# quad.net
KiCad netlist of a schematic drawn in EAGLE
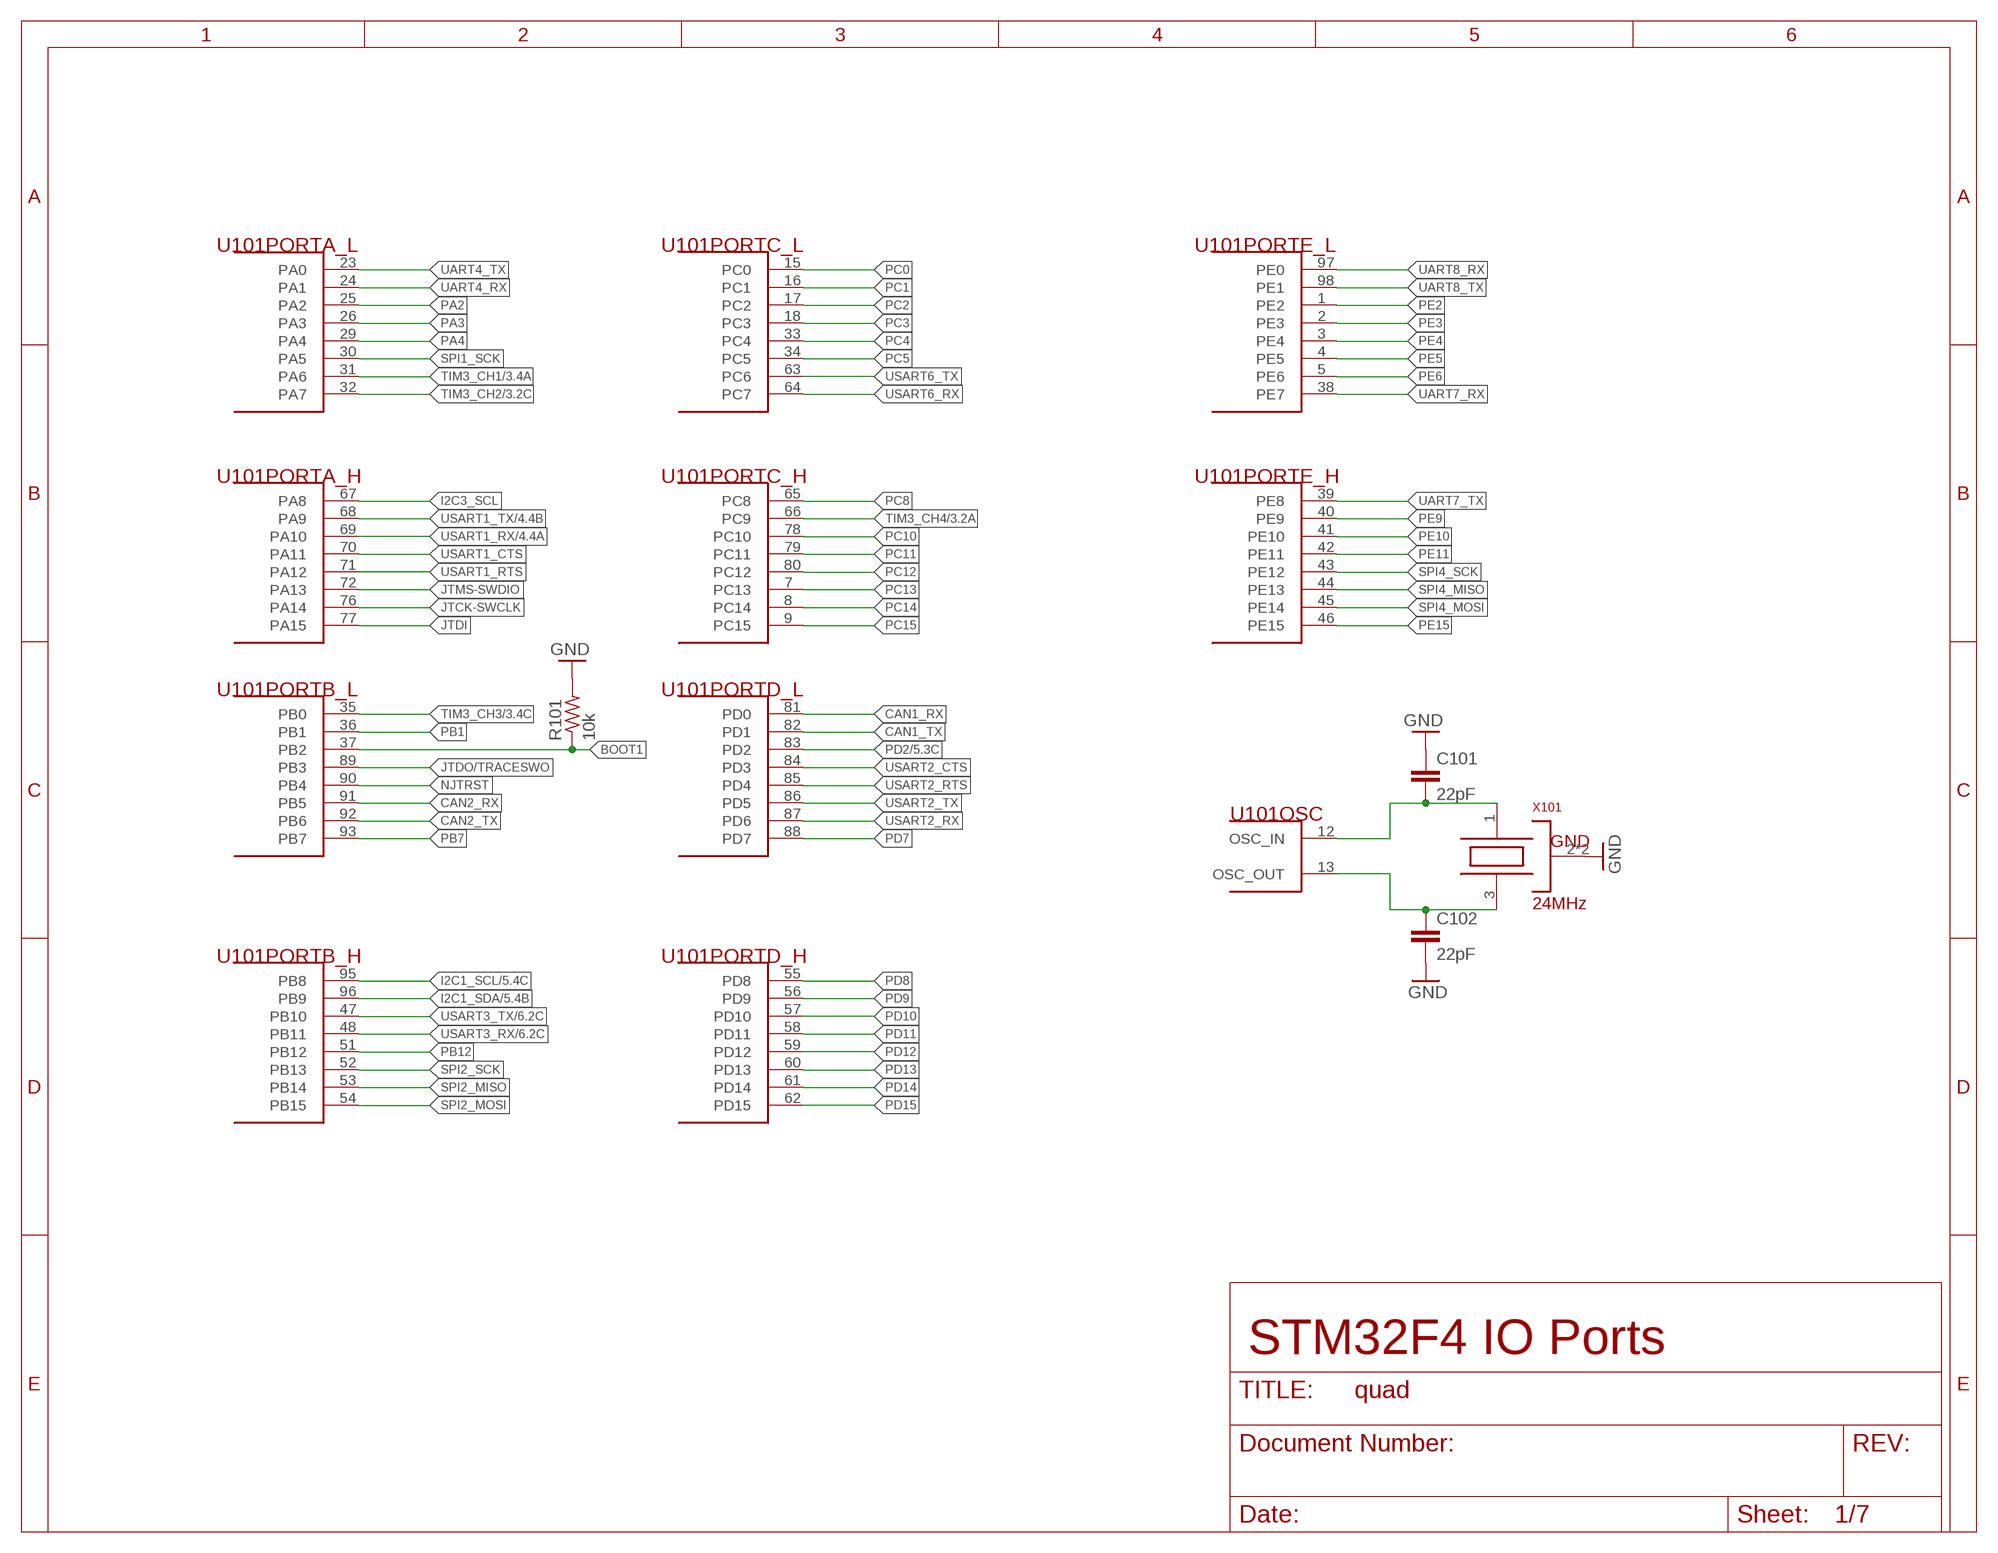
[diagram p0: schematic, sheet 1]
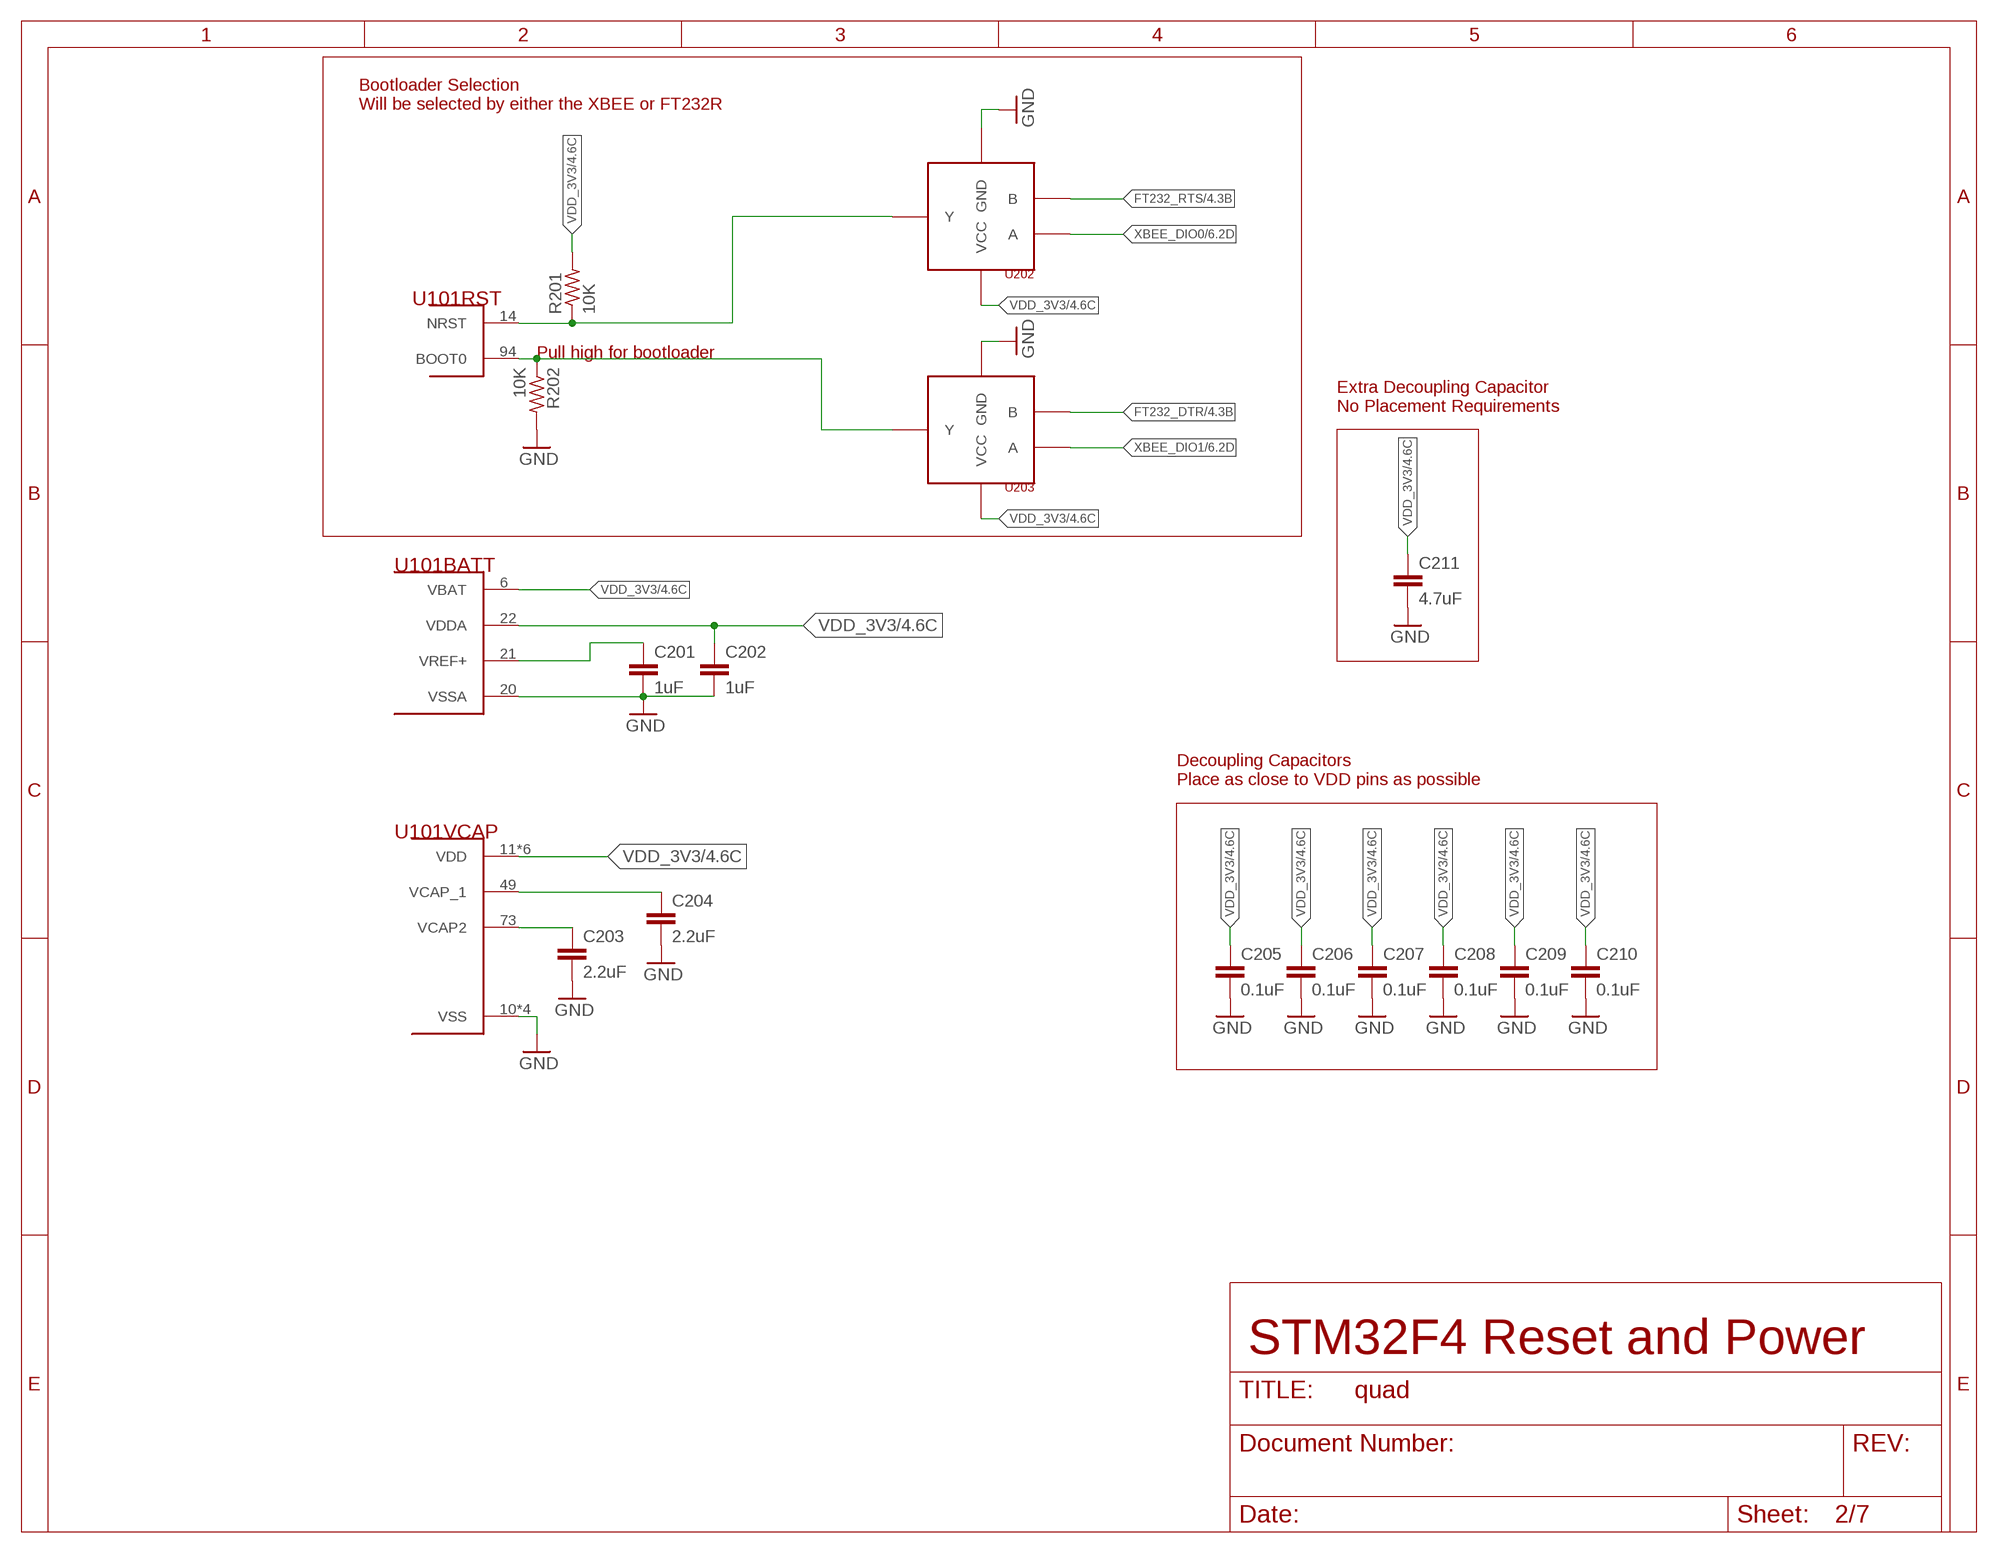
[diagram p1: schematic, sheet 2]
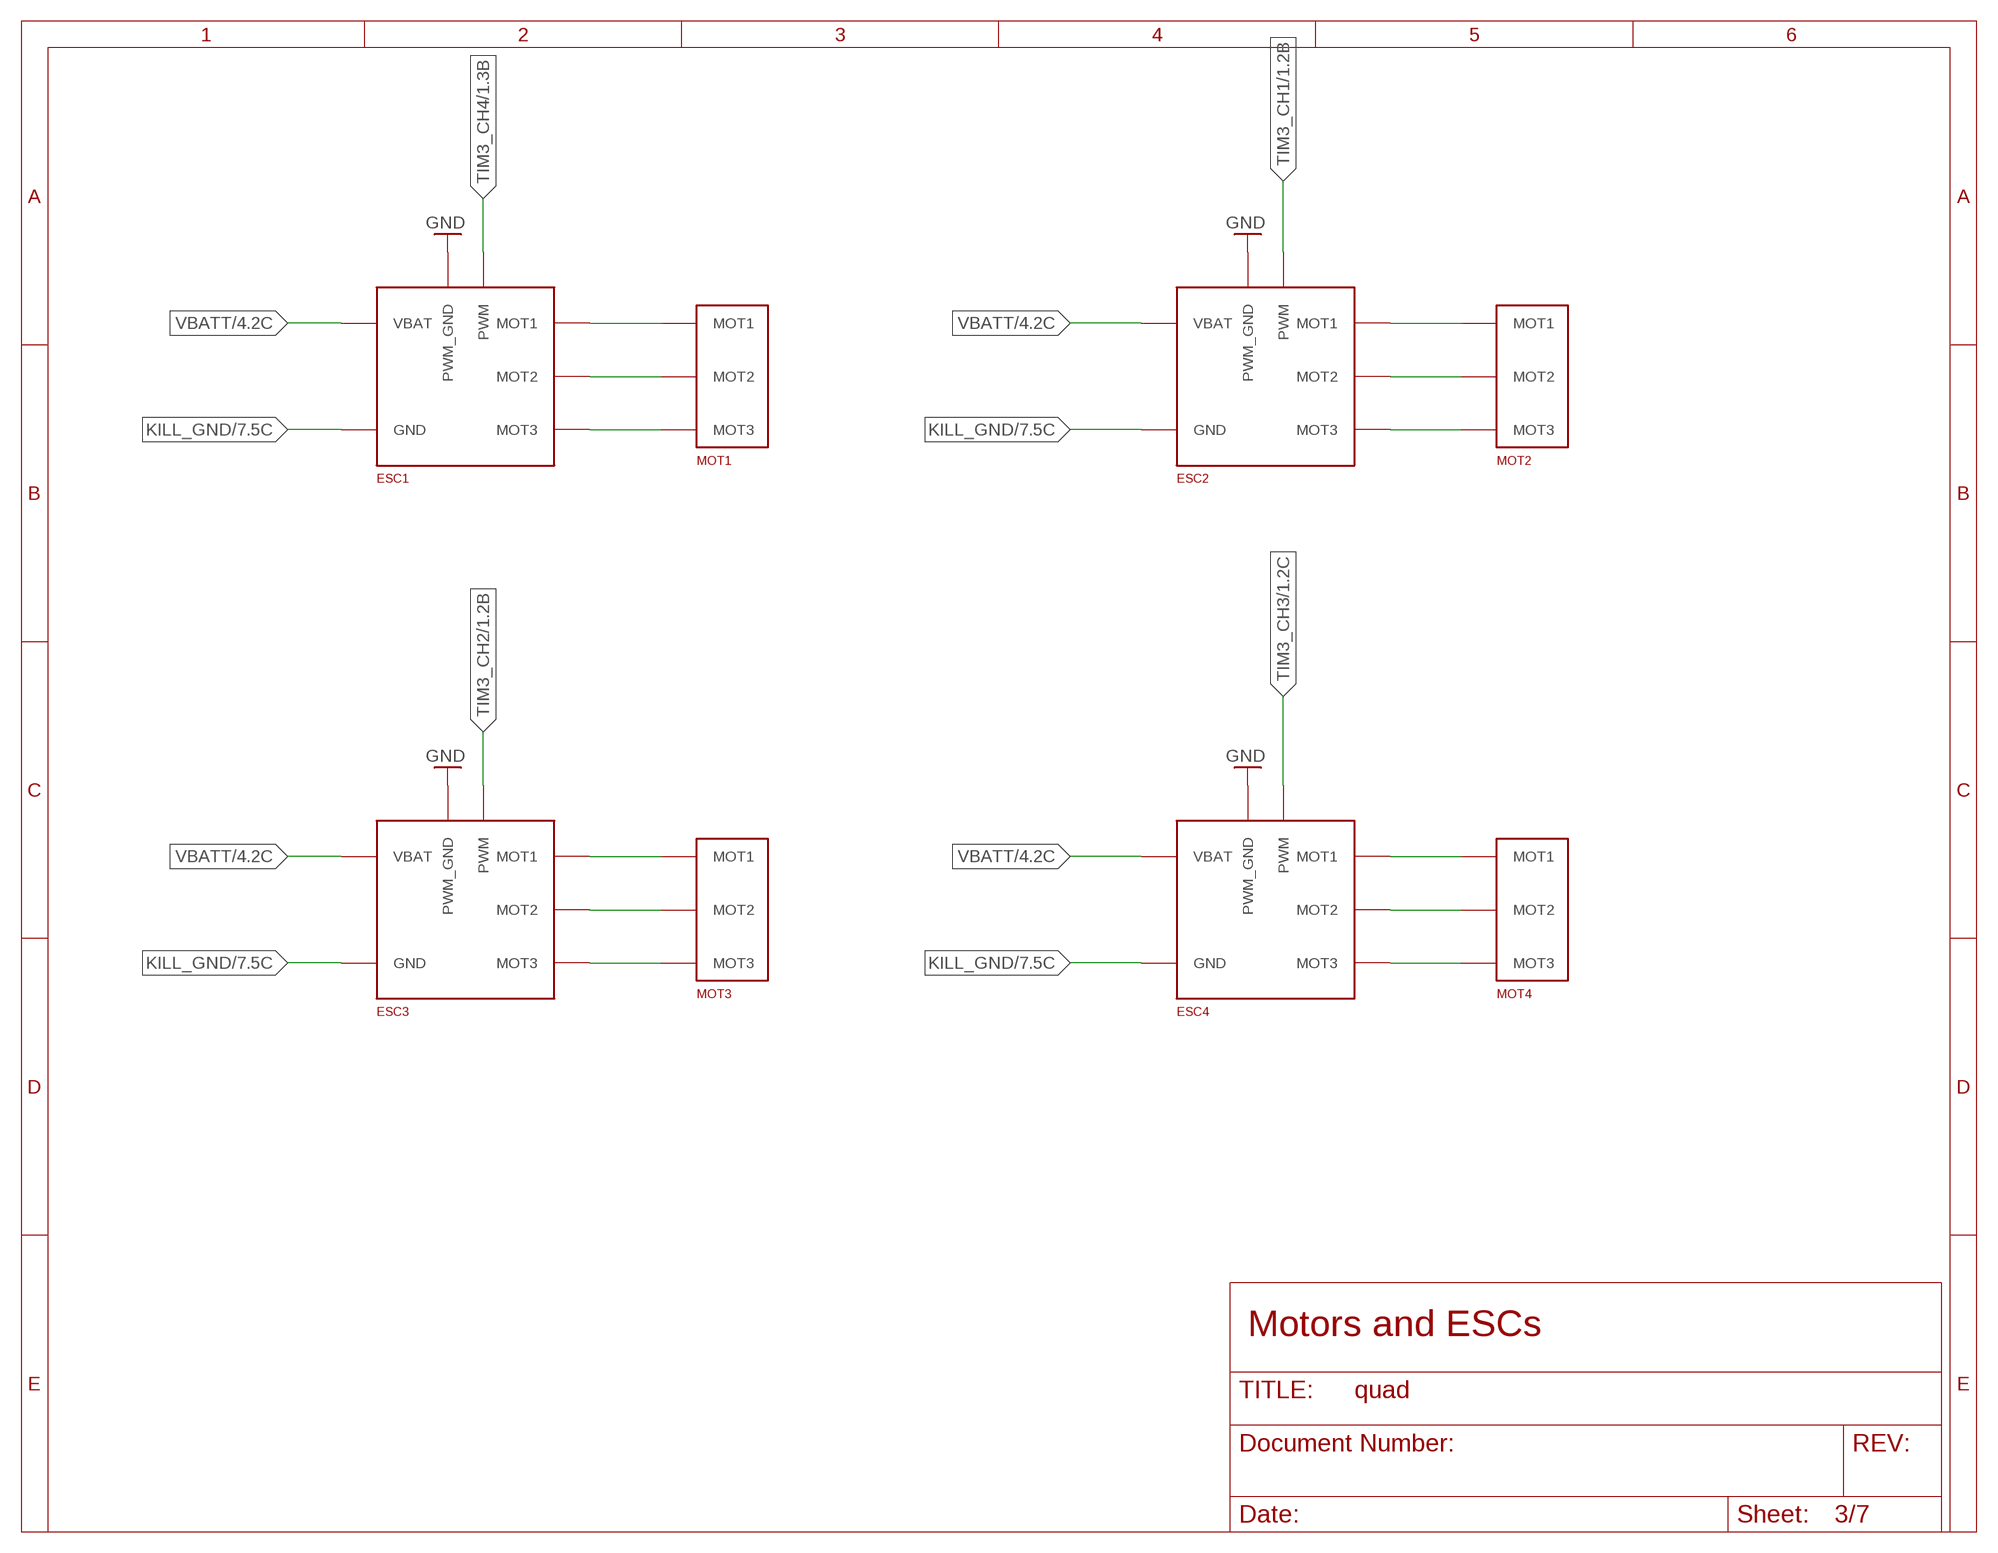
[diagram p2: schematic, sheet 3]
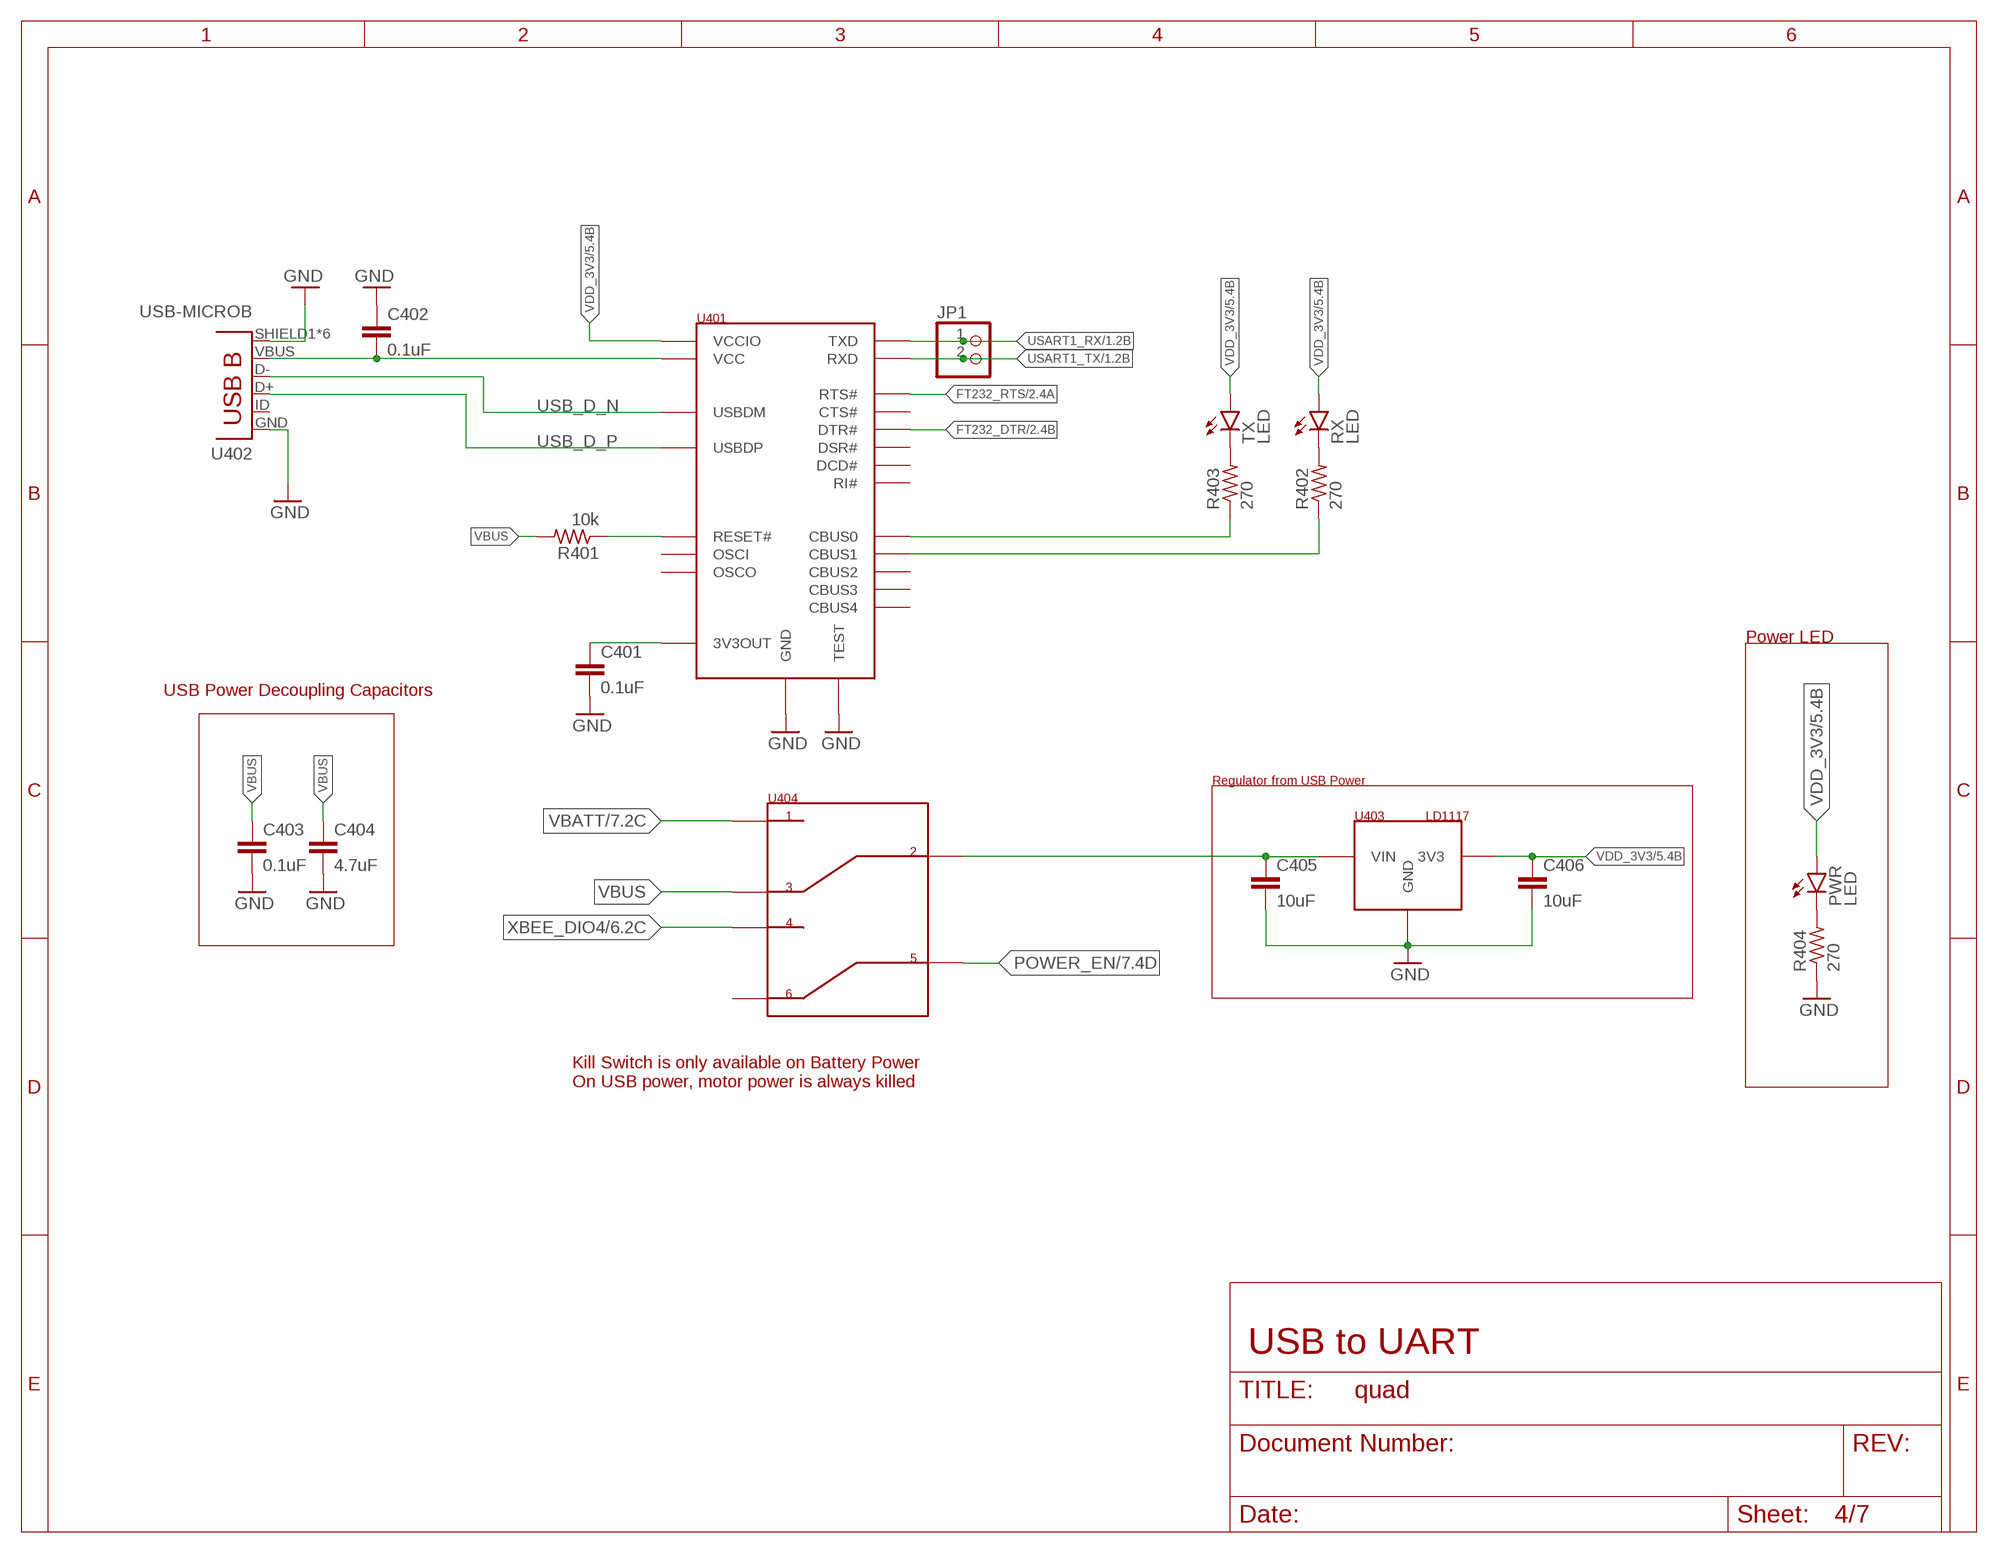
[diagram p3: schematic, sheet 4]
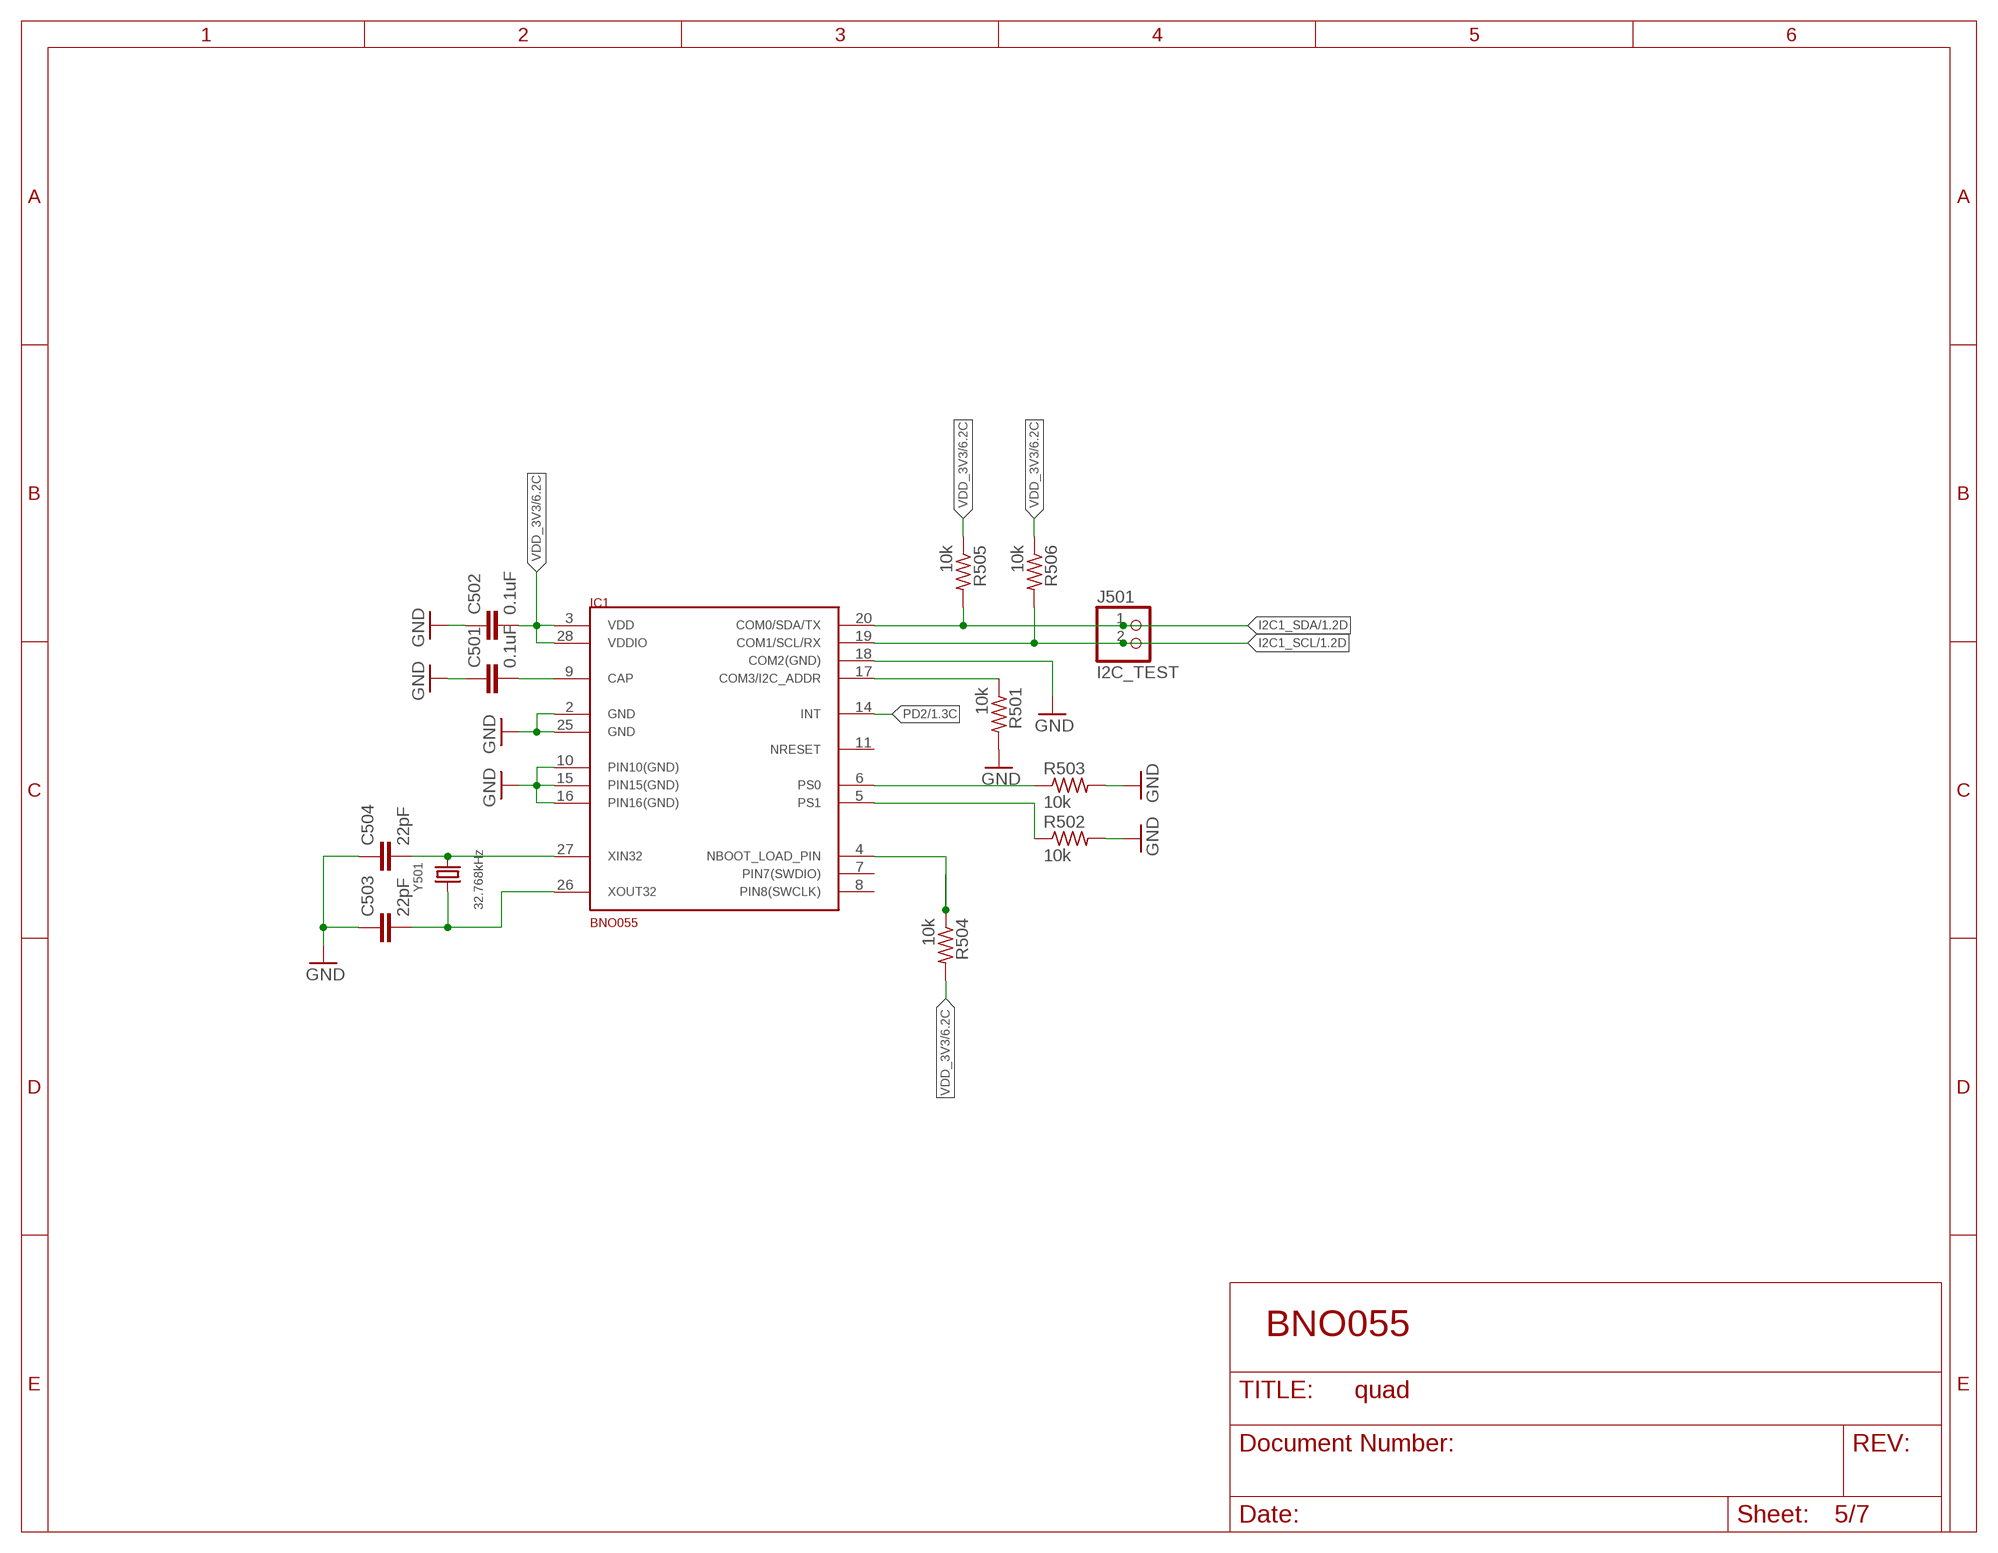
[diagram p4: schematic, sheet 5]
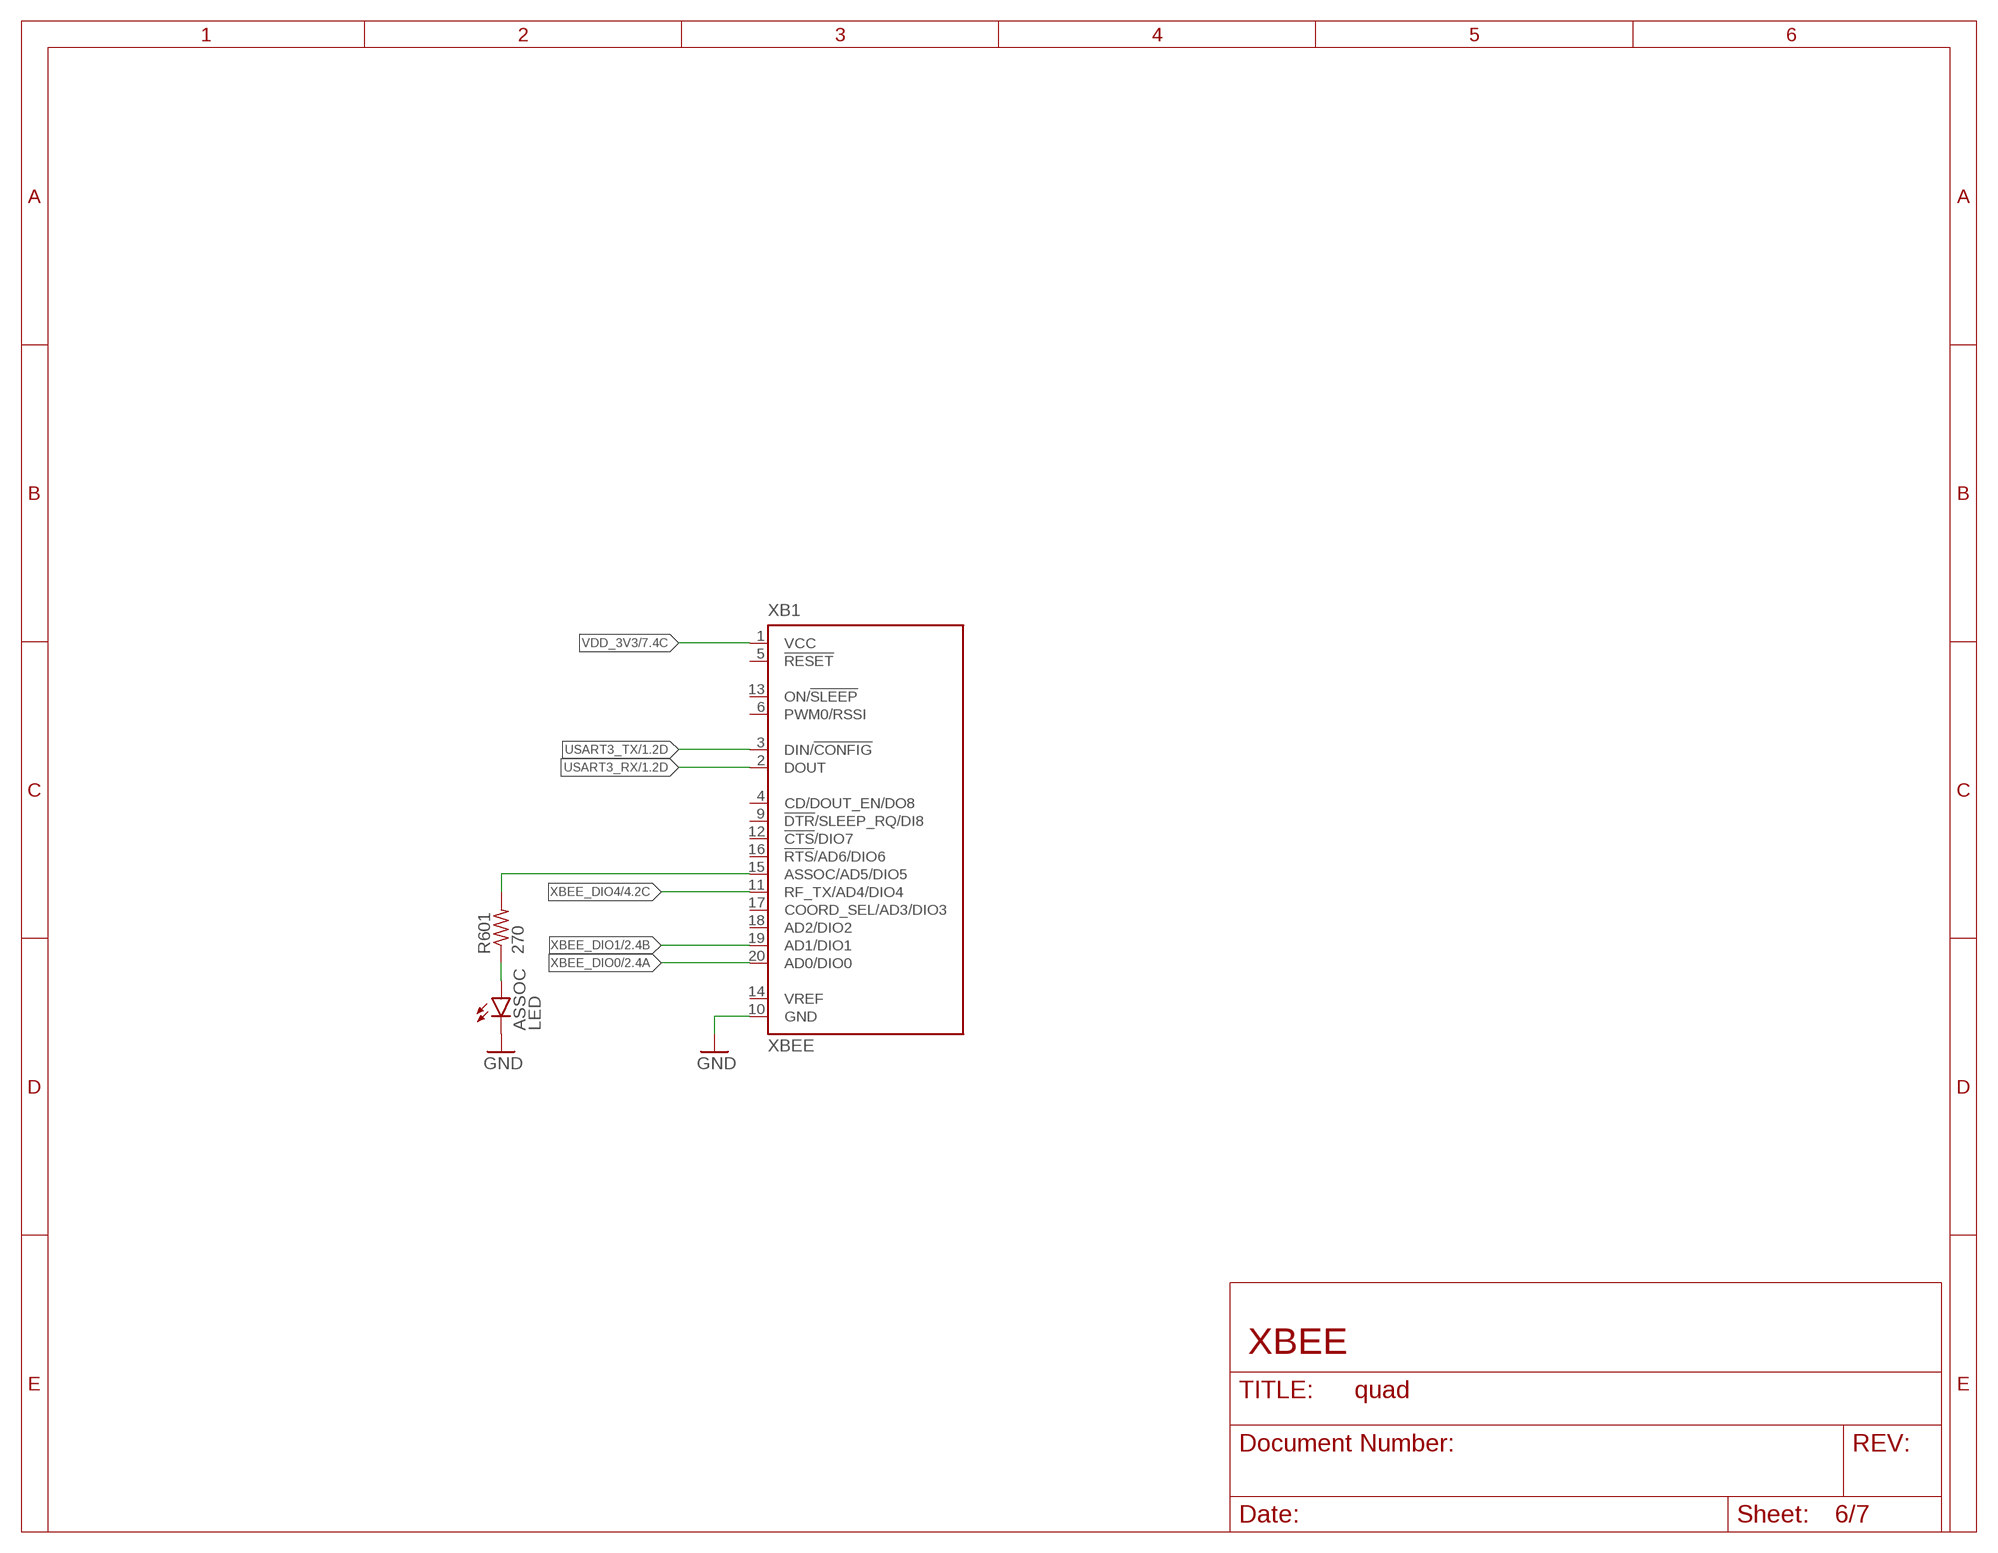
[diagram p5: schematic, sheet 6]
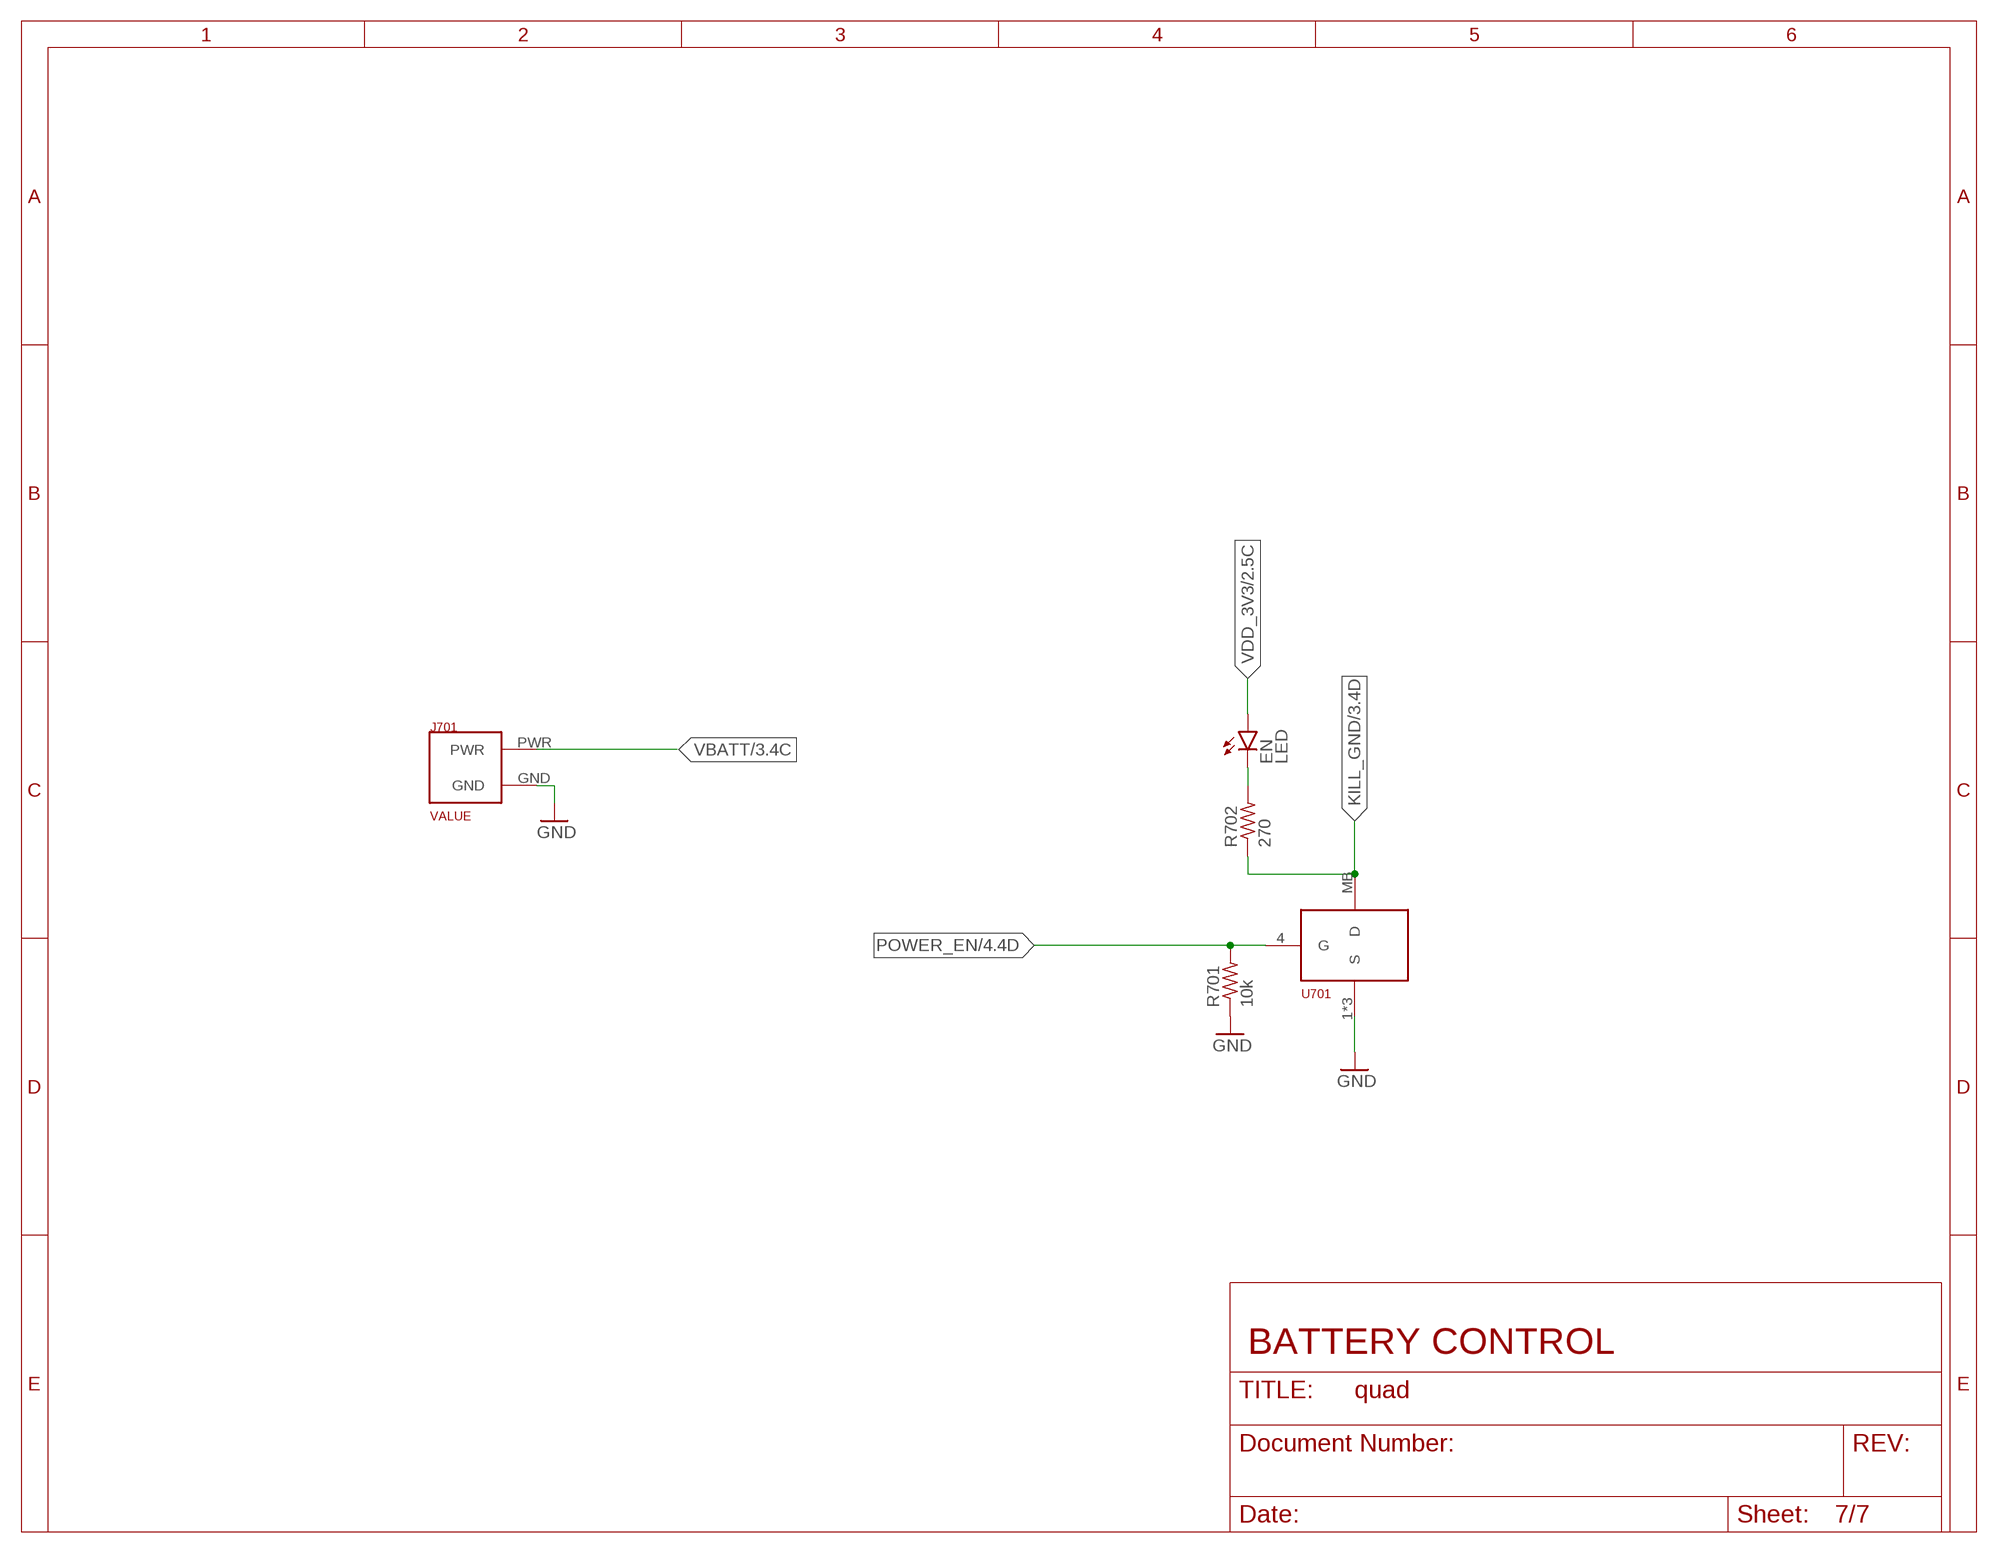
[diagram p6: schematic, sheet 7]

(export (version "E")
  (design (tool "Eeschema 10.0.6"))
  (components
    (comp (ref "C201")
      (value "1uF")
      (footprint "eagle-import:C0603")
      (libsource (lib "eagle-import") (part "C-EUC0603"))
    )
    (comp (ref "C202")
      (value "1uF")
      (footprint "eagle-import:C0603")
      (libsource (lib "eagle-import") (part "C-EUC0603"))
    )
    (comp (ref "C203")
      (value "2.2uF")
      (footprint "eagle-import:C0603")
      (libsource (lib "eagle-import") (part "C-EUC0603"))
    )
    (comp (ref "C204")
      (value "2.2uF")
      (footprint "eagle-import:C0603")
      (libsource (lib "eagle-import") (part "C-EUC0603"))
    )
    (comp (ref "C205")
      (value "0.1uF")
      (footprint "eagle-import:C0603")
      (libsource (lib "eagle-import") (part "C-EUC0603"))
    )
    (comp (ref "C206")
      (value "0.1uF")
      (footprint "eagle-import:C0603")
      (libsource (lib "eagle-import") (part "C-EUC0603"))
    )
    (comp (ref "C207")
      (value "0.1uF")
      (footprint "eagle-import:C0603")
      (libsource (lib "eagle-import") (part "C-EUC0603"))
    )
    (comp (ref "C208")
      (value "0.1uF")
      (footprint "eagle-import:C0603")
      (libsource (lib "eagle-import") (part "C-EUC0603"))
    )
    (comp (ref "C209")
      (value "0.1uF")
      (footprint "eagle-import:C0603")
      (libsource (lib "eagle-import") (part "C-EUC0603"))
    )
    (comp (ref "C210")
      (value "0.1uF")
      (footprint "eagle-import:C0603")
      (libsource (lib "eagle-import") (part "C-EUC0603"))
    )
    (comp (ref "C211")
      (value "4.7uF")
      (footprint "eagle-import:C0603")
      (libsource (lib "eagle-import") (part "C-EUC0603"))
    )
    (comp (ref "R201")
      (value "10K")
      (footprint "eagle-import:R0603")
      (libsource (lib "eagle-import") (part "R-US_R0603"))
    )
    (comp (ref "R202")
      (value "10K")
      (footprint "eagle-import:R0603")
      (libsource (lib "eagle-import") (part "R-US_R0603"))
    )
    (comp (ref "U101")
      (value "STM32F427VGT6")
      (footprint "eagle-import:LQFP-100")
      (libsource (lib "eagle-import") (part "STM32F427VGT6"))
    )
    (comp (ref "U202")
      (value "AND_GATE")
      (footprint "eagle-import:SOT23-5L")
      (libsource (lib "eagle-import") (part "AND_GATE"))
    )
    (comp (ref "U203")
      (value "SN74AHC1G32DBVR")
      (footprint "eagle-import:SOT23-5L")
      (libsource (lib "eagle-import") (part "SN74AHC1G32DBVR"))
    )
    (comp (ref "C401")
      (value "0.1uF")
      (footprint "eagle-import:C0603")
      (libsource (lib "eagle-import") (part "C-EUC0603"))
    )
    (comp (ref "C402")
      (value "0.1uF")
      (footprint "eagle-import:C0603")
      (libsource (lib "eagle-import") (part "C-EUC0603"))
    )
    (comp (ref "C403")
      (value "0.1uF")
      (footprint "eagle-import:C0603")
      (libsource (lib "eagle-import") (part "C-EUC0603"))
    )
    (comp (ref "C404")
      (value "4.7uF")
      (footprint "eagle-import:C0603")
      (libsource (lib "eagle-import") (part "C-EUC0603"))
    )
    (comp (ref "C405")
      (value "10uF")
      (footprint "eagle-import:C0603")
      (libsource (lib "eagle-import") (part "C-EUC0603"))
    )
    (comp (ref "C406")
      (value "10uF")
      (footprint "eagle-import:C0603")
      (libsource (lib "eagle-import") (part "C-EUC0603"))
    )
    (comp (ref "JP1")
      (value "PINHD-1X2")
      (footprint "eagle-import:1X02")
      (libsource (lib "eagle-import") (part "PINHD-1X2"))
    )
    (comp (ref "PWR")
      (value "LED")
      (footprint "eagle-import:LED-0603")
      (libsource (lib "eagle-import") (part "LED"))
    )
    (comp (ref "R401")
      (value "10k")
      (footprint "eagle-import:R0603")
      (libsource (lib "eagle-import") (part "R-US_R0603"))
    )
    (comp (ref "R402")
      (value "270")
      (footprint "eagle-import:R0603")
      (libsource (lib "eagle-import") (part "R-US_R0603"))
    )
    (comp (ref "R403")
      (value "270")
      (footprint "eagle-import:R0603")
      (libsource (lib "eagle-import") (part "R-US_R0603"))
    )
    (comp (ref "R404")
      (value "270")
      (footprint "eagle-import:R0603")
      (libsource (lib "eagle-import") (part "R-US_R0603"))
    )
    (comp (ref "RX")
      (value "LED")
      (footprint "eagle-import:LED-0603")
      (libsource (lib "eagle-import") (part "LED"))
    )
    (comp (ref "TX")
      (value "LED")
      (footprint "eagle-import:LED-0603")
      (libsource (lib "eagle-import") (part "LED"))
    )
    (comp (ref "U401")
      (value "FT232R")
      (footprint "eagle-import:SSOP28")
      (libsource (lib "eagle-import") (part "FT232R"))
    )
    (comp (ref "U402")
      (value "USB-MICROB")
      (footprint "eagle-import:USB-B-MICRO-SMD")
      (libsource (lib "eagle-import") (part "USB-MICROB"))
    )
    (comp (ref "U403")
      (value "LD1117")
      (footprint "eagle-import:SOT223")
      (libsource (lib "eagle-import") (part "LD1117"))
    )
    (comp (ref "U404")
      (value "MFS201N-16-Z")
      (footprint "eagle-import:MFS201N-16-Z")
      (libsource (lib "eagle-import") (part "MFS201N-16-Z"))
    )
    (comp (ref "EN")
      (value "LED")
      (footprint "eagle-import:LED-0603")
      (libsource (lib "eagle-import") (part "LED"))
    )
    (comp (ref "J701")
      (value "XT60")
      (footprint "eagle-import:XT60")
      (libsource (lib "eagle-import") (part "XT60"))
    )
    (comp (ref "R701")
      (value "10k")
      (footprint "eagle-import:R0603")
      (libsource (lib "eagle-import") (part "R-US_R0603"))
    )
    (comp (ref "R702")
      (value "270")
      (footprint "eagle-import:R0603")
      (libsource (lib "eagle-import") (part "R-US_R0603"))
    )
    (comp (ref "U701")
      (value "PSMN9RS-30YLC")
      (footprint "eagle-import:SOT669")
      (libsource (lib "eagle-import") (part "PSMN9RS-30YLC"))
    )
    (comp (ref "ESC1")
      (value "AFRO_ESC")
      (footprint "eagle-import:AFRO_ESC")
      (libsource (lib "eagle-import") (part "AFRO_ESC"))
    )
    (comp (ref "ESC2")
      (value "AFRO_ESC")
      (footprint "eagle-import:AFRO_ESC")
      (libsource (lib "eagle-import") (part "AFRO_ESC"))
    )
    (comp (ref "ESC3")
      (value "AFRO_ESC")
      (footprint "eagle-import:AFRO_ESC")
      (libsource (lib "eagle-import") (part "AFRO_ESC"))
    )
    (comp (ref "ESC4")
      (value "AFRO_ESC")
      (footprint "eagle-import:AFRO_ESC")
      (libsource (lib "eagle-import") (part "AFRO_ESC"))
    )
    (comp (ref "MOT1")
      (value "MOTOR")
      (footprint "eagle-import:MOTOR")
      (libsource (lib "eagle-import") (part "MOTOR"))
    )
    (comp (ref "MOT2")
      (value "MOTOR")
      (footprint "eagle-import:MOTOR")
      (libsource (lib "eagle-import") (part "MOTOR"))
    )
    (comp (ref "MOT3")
      (value "MOTOR")
      (footprint "eagle-import:MOTOR")
      (libsource (lib "eagle-import") (part "MOTOR"))
    )
    (comp (ref "MOT4")
      (value "MOTOR")
      (footprint "eagle-import:MOTOR")
      (libsource (lib "eagle-import") (part "MOTOR"))
    )
    (comp (ref "C501")
      (value "0.1uF")
      (footprint "eagle-import:C0603")
      (libsource (lib "eagle-import") (part "C-EUC0603"))
    )
    (comp (ref "C502")
      (value "0.1uF")
      (footprint "eagle-import:C0603")
      (libsource (lib "eagle-import") (part "C-EUC0603"))
    )
    (comp (ref "C503")
      (value "22pF")
      (footprint "eagle-import:C0603")
      (libsource (lib "eagle-import") (part "C-EUC0603"))
    )
    (comp (ref "C504")
      (value "22pF")
      (footprint "eagle-import:C0603")
      (libsource (lib "eagle-import") (part "C-EUC0603"))
    )
    (comp (ref "IC1")
      (value "BNO055")
      (footprint "eagle-import:LGA-28_3.80X5.20_0.5")
      (libsource (lib "eagle-import") (part "BNO055"))
    )
    (comp (ref "J501")
      (value "I2C_TEST")
      (footprint "eagle-import:1X02")
      (libsource (lib "eagle-import") (part "PINHD-1X2"))
    )
    (comp (ref "R501")
      (value "10k")
      (footprint "eagle-import:R0603")
      (libsource (lib "eagle-import") (part "R-US_R0603"))
    )
    (comp (ref "R502")
      (value "10k")
      (footprint "eagle-import:R0603")
      (libsource (lib "eagle-import") (part "R-US_R0603"))
    )
    (comp (ref "R503")
      (value "10k")
      (footprint "eagle-import:R0603")
      (libsource (lib "eagle-import") (part "R-US_R0603"))
    )
    (comp (ref "R504")
      (value "10k")
      (footprint "eagle-import:R0603")
      (libsource (lib "eagle-import") (part "R-US_R0603"))
    )
    (comp (ref "R505")
      (value "10k")
      (footprint "eagle-import:R0603")
      (libsource (lib "eagle-import") (part "R-US_R0603"))
    )
    (comp (ref "R506")
      (value "10k")
      (footprint "eagle-import:R0603")
      (libsource (lib "eagle-import") (part "R-US_R0603"))
    )
    (comp (ref "Y501")
      (value "32.768kHz")
      (footprint "eagle-import:ABS25")
      (libsource (lib "eagle-import") (part "CRYSTAL"))
    )
    (comp (ref "C101")
      (value "22pF")
      (footprint "eagle-import:C0603")
      (libsource (lib "eagle-import") (part "C-EUC0603"))
    )
    (comp (ref "C102")
      (value "22pF")
      (footprint "eagle-import:C0603")
      (libsource (lib "eagle-import") (part "C-EUC0603"))
    )
    (comp (ref "R101")
      (value "10k")
      (footprint "eagle-import:R0603")
      (libsource (lib "eagle-import") (part "R-US_R0603"))
    )
    (comp (ref "X101")
      (value "24MHz")
      (footprint "eagle-import:OSC3.2X2.5")
      (libsource (lib "eagle-import") (part "OSCILLATOR"))
    )
    (comp (ref "ASSOC")
      (value "LED")
      (footprint "eagle-import:LED-0603")
      (libsource (lib "eagle-import") (part "LED"))
    )
    (comp (ref "R601")
      (value "270")
      (footprint "eagle-import:R0603")
      (libsource (lib "eagle-import") (part "R-US_R0603"))
    )
    (comp (ref "XB1")
      (value "XBEE")
      (footprint "eagle-import:XBEE")
      (fields (field (name "MPN") "XBP24-Z7UIT-004"))
      (libsource (lib "eagle-import") (part "XBEE"))
    )
  )
  (nets
    (net (code "1") (name "BOOT1") (class "Default")
      (node (ref "R101") (pin "1") (pinfunction "1_1") (pintype "passive"))
      (node (ref "U101") (pin "37") (pinfunction "PB2_37") (pintype "power_in"))
    )
    (net (code "2") (name "CAN1_RX") (class "Default")
      (node (ref "U101") (pin "81") (pinfunction "PD0_81") (pintype "power_in"))
    )
    (net (code "3") (name "CAN1_TX") (class "Default")
      (node (ref "U101") (pin "82") (pinfunction "PD1_82") (pintype "power_in"))
    )
    (net (code "4") (name "CAN2_RX") (class "Default")
      (node (ref "U101") (pin "91") (pinfunction "PB5_91") (pintype "power_in"))
    )
    (net (code "5") (name "CAN2_TX") (class "Default")
      (node (ref "U101") (pin "92") (pinfunction "PB6_92") (pintype "power_in"))
    )
    (net (code "6") (name "FT232_DTR") (class "Default")
      (node (ref "U203") (pin "2") (pinfunction "B_2") (pintype "bidirectional"))
      (node (ref "U401") (pin "2") (pinfunction "DTR#_2") (pintype "bidirectional"))
    )
    (net (code "7") (name "FT232_RTS") (class "Default")
      (node (ref "U202") (pin "2") (pinfunction "B_2") (pintype "bidirectional"))
      (node (ref "U401") (pin "3") (pinfunction "RTS#_3") (pintype "bidirectional"))
    )
    (net (code "8") (name "GND") (class "Default")
      (node (ref "ASSOC") (pin "C") (pinfunction "C_C") (pintype "passive"))
      (node (ref "C101") (pin "1") (pinfunction "1_1") (pintype "passive"))
      (node (ref "C102") (pin "2") (pinfunction "2_2") (pintype "passive"))
      (node (ref "C201") (pin "2") (pinfunction "2_2") (pintype "passive"))
      (node (ref "C202") (pin "2") (pinfunction "2_2") (pintype "passive"))
      (node (ref "C203") (pin "2") (pinfunction "2_2") (pintype "passive"))
      (node (ref "C204") (pin "2") (pinfunction "2_2") (pintype "passive"))
      (node (ref "C205") (pin "2") (pinfunction "2_2") (pintype "passive"))
      (node (ref "C206") (pin "2") (pinfunction "2_2") (pintype "passive"))
      (node (ref "C207") (pin "2") (pinfunction "2_2") (pintype "passive"))
      (node (ref "C208") (pin "2") (pinfunction "2_2") (pintype "passive"))
      (node (ref "C209") (pin "2") (pinfunction "2_2") (pintype "passive"))
      (node (ref "C210") (pin "2") (pinfunction "2_2") (pintype "passive"))
      (node (ref "C211") (pin "2") (pinfunction "2_2") (pintype "passive"))
      (node (ref "C401") (pin "2") (pinfunction "2_2") (pintype "passive"))
      (node (ref "C402") (pin "1") (pinfunction "1_1") (pintype "passive"))
      (node (ref "C403") (pin "2") (pinfunction "2_2") (pintype "passive"))
      (node (ref "C404") (pin "2") (pinfunction "2_2") (pintype "passive"))
      (node (ref "C405") (pin "2") (pinfunction "2_2") (pintype "passive"))
      (node (ref "C406") (pin "2") (pinfunction "2_2") (pintype "passive"))
      (node (ref "C501") (pin "1") (pinfunction "1_1") (pintype "passive"))
      (node (ref "C502") (pin "1") (pinfunction "1_1") (pintype "passive"))
      (node (ref "C503") (pin "1") (pinfunction "1_1") (pintype "passive"))
      (node (ref "C504") (pin "1") (pinfunction "1_1") (pintype "passive"))
      (node (ref "ESC1") (pin "PWM_GND") (pinfunction "PWM_GND_PWM_GND") (pintype "bidirectional"))
      (node (ref "ESC2") (pin "PWM_GND") (pinfunction "PWM_GND_PWM_GND") (pintype "bidirectional"))
      (node (ref "ESC3") (pin "PWM_GND") (pinfunction "PWM_GND_PWM_GND") (pintype "bidirectional"))
      (node (ref "ESC4") (pin "PWM_GND") (pinfunction "PWM_GND_PWM_GND") (pintype "bidirectional"))
      (node (ref "IC1") (pin "10") (pinfunction "10_10") (pintype "bidirectional"))
      (node (ref "IC1") (pin "15") (pinfunction "15_15") (pintype "bidirectional"))
      (node (ref "IC1") (pin "16") (pinfunction "16_16") (pintype "bidirectional"))
      (node (ref "IC1") (pin "18") (pinfunction "18_18") (pintype "bidirectional"))
      (node (ref "IC1") (pin "2") (pinfunction "2_2") (pintype "bidirectional"))
      (node (ref "IC1") (pin "25") (pinfunction "25_25") (pintype "bidirectional"))
      (node (ref "J701") (pin "GND") (pinfunction "GND_GND") (pintype "bidirectional"))
      (node (ref "R101") (pin "2") (pinfunction "2_2") (pintype "passive"))
      (node (ref "R202") (pin "2") (pinfunction "2_2") (pintype "passive"))
      (node (ref "R404") (pin "1") (pinfunction "1_1") (pintype "passive"))
      (node (ref "R501") (pin "2") (pinfunction "2_2") (pintype "passive"))
      (node (ref "R502") (pin "2") (pinfunction "2_2") (pintype "passive"))
      (node (ref "R503") (pin "2") (pinfunction "2_2") (pintype "passive"))
      (node (ref "R701") (pin "1") (pinfunction "1_1") (pintype "passive"))
      (node (ref "U101") (pin "10") (pinfunction "VSS_10") (pintype "power_in"))
      (node (ref "U101") (pin "20") (pinfunction "VSSA_20") (pintype "power_in"))
      (node (ref "U101") (pin "27") (pinfunction "VSS_27") (pintype "power_in"))
      (node (ref "U101") (pin "74") (pinfunction "VSS_74") (pintype "power_in"))
      (node (ref "U101") (pin "99") (pinfunction "VSS_99") (pintype "power_in"))
      (node (ref "U202") (pin "3") (pinfunction "GND_3") (pintype "bidirectional"))
      (node (ref "U203") (pin "3") (pinfunction "GND_3") (pintype "bidirectional"))
      (node (ref "U401") (pin "18") (pinfunction "GND_18") (pintype "bidirectional"))
      (node (ref "U401") (pin "21") (pinfunction "GND_21") (pintype "bidirectional"))
      (node (ref "U401") (pin "25") (pinfunction "GND_25") (pintype "bidirectional"))
      (node (ref "U401") (pin "26") (pinfunction "TEST_26") (pintype "bidirectional"))
      (node (ref "U401") (pin "7") (pinfunction "GND_7") (pintype "bidirectional"))
      (node (ref "U402") (pin "GND") (pinfunction "GND_GND") (pintype "bidirectional"))
      (node (ref "U402") (pin "SHIELD1") (pinfunction "SHIELD_SHIELD1") (pintype "bidirectional"))
      (node (ref "U402") (pin "SHIELD2") (pinfunction "SHIELD_SHIELD2") (pintype "bidirectional"))
      (node (ref "U402") (pin "SHIELD3") (pinfunction "SHIELD_SHIELD3") (pintype "bidirectional"))
      (node (ref "U402") (pin "SHIELD4") (pinfunction "SHIELD_SHIELD4") (pintype "bidirectional"))
      (node (ref "U402") (pin "SHIELD5") (pinfunction "SHIELD_SHIELD5") (pintype "bidirectional"))
      (node (ref "U402") (pin "SHIELD6") (pinfunction "SHIELD_SHIELD6") (pintype "bidirectional"))
      (node (ref "U403") (pin "1") (pinfunction "GND_1") (pintype "bidirectional"))
      (node (ref "U701") (pin "1") (pinfunction "S_1") (pintype "bidirectional"))
      (node (ref "U701") (pin "2") (pinfunction "S_2") (pintype "bidirectional"))
      (node (ref "U701") (pin "3") (pinfunction "S_3") (pintype "bidirectional"))
      (node (ref "X101") (pin "2") (pinfunction "GND_2") (pintype "power_in"))
      (node (ref "X101") (pin "4") (pinfunction "GND_4") (pintype "power_in"))
      (node (ref "XB1") (pin "10") (pinfunction "GND_10") (pintype "power_in"))
    )
    (net (code "9") (name "I2C1_SCL") (class "Default")
      (node (ref "IC1") (pin "19") (pinfunction "19_19") (pintype "bidirectional"))
      (node (ref "J501") (pin "2") (pinfunction "2_2") (pintype "passive"))
      (node (ref "R506") (pin "2") (pinfunction "2_2") (pintype "passive"))
      (node (ref "U101") (pin "95") (pinfunction "PB8_95") (pintype "power_in"))
    )
    (net (code "10") (name "I2C1_SDA") (class "Default")
      (node (ref "IC1") (pin "20") (pinfunction "20_20") (pintype "bidirectional"))
      (node (ref "J501") (pin "1") (pinfunction "1_1") (pintype "passive"))
      (node (ref "R505") (pin "2") (pinfunction "2_2") (pintype "passive"))
      (node (ref "U101") (pin "96") (pinfunction "PB9_96") (pintype "power_in"))
    )
    (net (code "11") (name "I2C3_SCL") (class "Default")
      (node (ref "U101") (pin "67") (pinfunction "PA8_67") (pintype "power_in"))
    )
    (net (code "12") (name "JTCK-SWCLK") (class "Default")
      (node (ref "U101") (pin "76") (pinfunction "PA14_76") (pintype "power_in"))
    )
    (net (code "13") (name "JTDI") (class "Default")
      (node (ref "U101") (pin "77") (pinfunction "PA15_77") (pintype "power_in"))
    )
    (net (code "14") (name "JTDO{slash}TRACESWO") (class "Default")
      (node (ref "U101") (pin "89") (pinfunction "PB3_89") (pintype "power_in"))
    )
    (net (code "15") (name "JTMS-SWDIO") (class "Default")
      (node (ref "U101") (pin "72") (pinfunction "PA13_72") (pintype "power_in"))
    )
    (net (code "16") (name "KILL_GND") (class "Default")
      (node (ref "ESC1") (pin "GND") (pinfunction "GND_GND") (pintype "bidirectional"))
      (node (ref "ESC2") (pin "GND") (pinfunction "GND_GND") (pintype "bidirectional"))
      (node (ref "ESC3") (pin "GND") (pinfunction "GND_GND") (pintype "bidirectional"))
      (node (ref "ESC4") (pin "GND") (pinfunction "GND_GND") (pintype "bidirectional"))
      (node (ref "R702") (pin "1") (pinfunction "1_1") (pintype "passive"))
      (node (ref "U701") (pin "MB") (pinfunction "D_MB") (pintype "bidirectional"))
    )
    (net (code "17") (name "NJTRST") (class "Default")
      (node (ref "U101") (pin "90") (pinfunction "PB4_90") (pintype "power_in"))
    )
    (net (code "18") (name "Net-(ASSOC-PadA)") (class "Default")
      (node (ref "ASSOC") (pin "A") (pinfunction "A_A") (pintype "passive"))
      (node (ref "R601") (pin "1") (pinfunction "1_1") (pintype "passive"))
    )
    (net (code "19") (name "Net-(C501-Pad2)") (class "Default")
      (node (ref "C501") (pin "2") (pinfunction "2_2") (pintype "passive"))
      (node (ref "IC1") (pin "9") (pinfunction "9_9") (pintype "bidirectional"))
    )
    (net (code "20") (name "Net-(C503-Pad2)") (class "Default")
      (node (ref "C503") (pin "2") (pinfunction "2_2") (pintype "passive"))
      (node (ref "IC1") (pin "26") (pinfunction "26_26") (pintype "bidirectional"))
      (node (ref "Y501") (pin "1") (pinfunction "1_1") (pintype "passive"))
    )
    (net (code "21") (name "Net-(EN-PadC)") (class "Default")
      (node (ref "EN") (pin "C") (pinfunction "C_C") (pintype "passive"))
      (node (ref "R702") (pin "2") (pinfunction "2_2") (pintype "passive"))
    )
    (net (code "22") (name "Net-(ESC1-PadMOT1)") (class "Default")
      (node (ref "ESC1") (pin "MOT1") (pinfunction "MOT1_MOT1") (pintype "bidirectional"))
      (node (ref "MOT1") (pin "MOT1") (pinfunction "MOT1_MOT1") (pintype "bidirectional"))
    )
    (net (code "23") (name "Net-(ESC1-PadMOT2)") (class "Default")
      (node (ref "ESC1") (pin "MOT2") (pinfunction "MOT2_MOT2") (pintype "bidirectional"))
      (node (ref "MOT1") (pin "MOT2") (pinfunction "MOT2_MOT2") (pintype "bidirectional"))
    )
    (net (code "24") (name "Net-(ESC1-PadMOT3)") (class "Default")
      (node (ref "ESC1") (pin "MOT3") (pinfunction "MOT3_MOT3") (pintype "bidirectional"))
      (node (ref "MOT1") (pin "MOT3") (pinfunction "MOT3_MOT3") (pintype "bidirectional"))
    )
    (net (code "25") (name "Net-(ESC2-PadMOT1)") (class "Default")
      (node (ref "ESC2") (pin "MOT1") (pinfunction "MOT1_MOT1") (pintype "bidirectional"))
      (node (ref "MOT2") (pin "MOT1") (pinfunction "MOT1_MOT1") (pintype "bidirectional"))
    )
    (net (code "26") (name "Net-(ESC2-PadMOT2)") (class "Default")
      (node (ref "ESC2") (pin "MOT2") (pinfunction "MOT2_MOT2") (pintype "bidirectional"))
      (node (ref "MOT2") (pin "MOT2") (pinfunction "MOT2_MOT2") (pintype "bidirectional"))
    )
    (net (code "27") (name "Net-(ESC2-PadMOT3)") (class "Default")
      (node (ref "ESC2") (pin "MOT3") (pinfunction "MOT3_MOT3") (pintype "bidirectional"))
      (node (ref "MOT2") (pin "MOT3") (pinfunction "MOT3_MOT3") (pintype "bidirectional"))
    )
    (net (code "28") (name "Net-(ESC3-PadMOT1)") (class "Default")
      (node (ref "ESC3") (pin "MOT1") (pinfunction "MOT1_MOT1") (pintype "bidirectional"))
      (node (ref "MOT3") (pin "MOT1") (pinfunction "MOT1_MOT1") (pintype "bidirectional"))
    )
    (net (code "29") (name "Net-(ESC3-PadMOT2)") (class "Default")
      (node (ref "ESC3") (pin "MOT2") (pinfunction "MOT2_MOT2") (pintype "bidirectional"))
      (node (ref "MOT3") (pin "MOT2") (pinfunction "MOT2_MOT2") (pintype "bidirectional"))
    )
    (net (code "30") (name "Net-(ESC3-PadMOT3)") (class "Default")
      (node (ref "ESC3") (pin "MOT3") (pinfunction "MOT3_MOT3") (pintype "bidirectional"))
      (node (ref "MOT3") (pin "MOT3") (pinfunction "MOT3_MOT3") (pintype "bidirectional"))
    )
    (net (code "31") (name "Net-(ESC4-PadMOT1)") (class "Default")
      (node (ref "ESC4") (pin "MOT1") (pinfunction "MOT1_MOT1") (pintype "bidirectional"))
      (node (ref "MOT4") (pin "MOT1") (pinfunction "MOT1_MOT1") (pintype "bidirectional"))
    )
    (net (code "32") (name "Net-(ESC4-PadMOT2)") (class "Default")
      (node (ref "ESC4") (pin "MOT2") (pinfunction "MOT2_MOT2") (pintype "bidirectional"))
      (node (ref "MOT4") (pin "MOT2") (pinfunction "MOT2_MOT2") (pintype "bidirectional"))
    )
    (net (code "33") (name "Net-(ESC4-PadMOT3)") (class "Default")
      (node (ref "ESC4") (pin "MOT3") (pinfunction "MOT3_MOT3") (pintype "bidirectional"))
      (node (ref "MOT4") (pin "MOT3") (pinfunction "MOT3_MOT3") (pintype "bidirectional"))
    )
    (net (code "34") (name "Net-(IC1-Pad4)") (class "Default")
      (node (ref "IC1") (pin "4") (pinfunction "4_4") (pintype "bidirectional"))
      (node (ref "R504") (pin "1") (pinfunction "1_1") (pintype "passive"))
    )
    (net (code "35") (name "Net-(IC1-Pad5)") (class "Default")
      (node (ref "IC1") (pin "5") (pinfunction "5_5") (pintype "bidirectional"))
      (node (ref "R502") (pin "1") (pinfunction "1_1") (pintype "passive"))
    )
    (net (code "36") (name "Net-(IC1-Pad6)") (class "Default")
      (node (ref "IC1") (pin "6") (pinfunction "6_6") (pintype "bidirectional"))
      (node (ref "R503") (pin "1") (pinfunction "1_1") (pintype "passive"))
    )
    (net (code "37") (name "Net-(IC1-Pad17)") (class "Default")
      (node (ref "IC1") (pin "17") (pinfunction "17_17") (pintype "bidirectional"))
      (node (ref "R501") (pin "1") (pinfunction "1_1") (pintype "passive"))
    )
    (net (code "38") (name "Net-(PWR-PadC)") (class "Default")
      (node (ref "PWR") (pin "C") (pinfunction "C_C") (pintype "passive"))
      (node (ref "R404") (pin "2") (pinfunction "2_2") (pintype "passive"))
    )
    (net (code "39") (name "Net-(R402-Pad2)") (class "Default")
      (node (ref "R402") (pin "2") (pinfunction "2_2") (pintype "passive"))
      (node (ref "RX") (pin "C") (pinfunction "C_C") (pintype "passive"))
    )
    (net (code "40") (name "Net-(R403-Pad2)") (class "Default")
      (node (ref "R403") (pin "2") (pinfunction "2_2") (pintype "passive"))
      (node (ref "TX") (pin "C") (pinfunction "C_C") (pintype "passive"))
    )
    (net (code "41") (name "Net-(U101B-OSC_IN)") (class "Default")
      (node (ref "C101") (pin "2") (pinfunction "2_2") (pintype "passive"))
      (node (ref "U101") (pin "12") (pinfunction "OSC_IN_12") (pintype "power_in"))
      (node (ref "X101") (pin "1") (pinfunction "OSC1_1") (pintype "bidirectional"))
    )
    (net (code "42") (name "Net-(U101B-OSC_OUT)") (class "Default")
      (node (ref "C102") (pin "1") (pinfunction "1_1") (pintype "passive"))
      (node (ref "U101") (pin "13") (pinfunction "OSC_OUT_13") (pintype "power_in"))
      (node (ref "X101") (pin "3") (pinfunction "OSC2_3") (pintype "bidirectional"))
    )
    (net (code "43") (name "Net-(U101M-BOOT0)") (class "Default")
      (node (ref "R202") (pin "1") (pinfunction "1_1") (pintype "passive"))
      (node (ref "U101") (pin "94") (pinfunction "BOOT0_94") (pintype "power_in"))
      (node (ref "U203") (pin "4") (pinfunction "Y_4") (pintype "bidirectional"))
    )
    (net (code "44") (name "Net-(U101M-NRST)") (class "Default")
      (node (ref "R201") (pin "1") (pinfunction "1_1") (pintype "passive"))
      (node (ref "U101") (pin "14") (pinfunction "NRST_14") (pintype "power_in"))
      (node (ref "U202") (pin "4") (pinfunction "Y_4") (pintype "bidirectional"))
    )
    (net (code "45") (name "Net-(U101N-VCAP2)") (class "Default")
      (node (ref "C203") (pin "1") (pinfunction "1_1") (pintype "passive"))
      (node (ref "U101") (pin "73") (pinfunction "VCAP2_73") (pintype "power_in"))
    )
    (net (code "46") (name "Net-(U101N-VCAP_1)") (class "Default")
      (node (ref "C204") (pin "1") (pinfunction "1_1") (pintype "passive"))
      (node (ref "U101") (pin "49") (pinfunction "VCAP_1_49") (pintype "power_in"))
    )
    (net (code "47") (name "Net-(U401-3V3OUT)") (class "Default")
      (node (ref "C401") (pin "1") (pinfunction "1_1") (pintype "passive"))
      (node (ref "U401") (pin "17") (pinfunction "3V3OUT_17") (pintype "bidirectional"))
    )
    (net (code "48") (name "Net-(U401-CBUS0)") (class "Default")
      (node (ref "R403") (pin "1") (pinfunction "1_1") (pintype "passive"))
      (node (ref "U401") (pin "23") (pinfunction "CBUS0_23") (pintype "bidirectional"))
    )
    (net (code "49") (name "Net-(U401-CBUS1)") (class "Default")
      (node (ref "R402") (pin "1") (pinfunction "1_1") (pintype "passive"))
      (node (ref "U401") (pin "22") (pinfunction "CBUS1_22") (pintype "bidirectional"))
    )
    (net (code "50") (name "Net-(U401-RESET#)") (class "Default")
      (node (ref "R401") (pin "1") (pinfunction "1_1") (pintype "passive"))
      (node (ref "U401") (pin "19") (pinfunction "RESET#_19") (pintype "bidirectional"))
    )
    (net (code "51") (name "Net-(U403-VIN)") (class "Default")
      (node (ref "C405") (pin "1") (pinfunction "1_1") (pintype "passive"))
      (node (ref "U403") (pin "3") (pinfunction "VIN_3") (pintype "bidirectional"))
      (node (ref "U404") (pin "2") (pinfunction "2_2") (pintype "bidirectional"))
    )
    (net (code "52") (name "Net-(XB1-ASSOC{slash}AD5{slash}DIO5)") (class "Default")
      (node (ref "R601") (pin "2") (pinfunction "2_2") (pintype "passive"))
      (node (ref "XB1") (pin "15") (pinfunction "ASSOC/AD5/DIO5_15") (pintype "bidirectional"))
    )
    (net (code "53") (name "Net-(Y501-2)") (class "Default")
      (node (ref "C504") (pin "2") (pinfunction "2_2") (pintype "passive"))
      (node (ref "IC1") (pin "27") (pinfunction "27_27") (pintype "bidirectional"))
      (node (ref "Y501") (pin "4") (pinfunction "2_4") (pintype "passive"))
    )
    (net (code "54") (name "PA2") (class "Default")
      (node (ref "U101") (pin "25") (pinfunction "PA2_25") (pintype "power_in"))
    )
    (net (code "55") (name "PA3") (class "Default")
      (node (ref "U101") (pin "26") (pinfunction "PA3_26") (pintype "power_in"))
    )
    (net (code "56") (name "PA4") (class "Default")
      (node (ref "U101") (pin "29") (pinfunction "PA4_29") (pintype "power_in"))
    )
    (net (code "57") (name "PB1") (class "Default")
      (node (ref "U101") (pin "36") (pinfunction "PB1_36") (pintype "power_in"))
    )
    (net (code "58") (name "PB7") (class "Default")
      (node (ref "U101") (pin "93") (pinfunction "PB7_93") (pintype "power_in"))
    )
    (net (code "59") (name "PB12") (class "Default")
      (node (ref "U101") (pin "51") (pinfunction "PB12_51") (pintype "power_in"))
    )
    (net (code "60") (name "PC0") (class "Default")
      (node (ref "U101") (pin "15") (pinfunction "PC0_15") (pintype "power_in"))
    )
    (net (code "61") (name "PC1") (class "Default")
      (node (ref "U101") (pin "16") (pinfunction "PC1_16") (pintype "power_in"))
    )
    (net (code "62") (name "PC2") (class "Default")
      (node (ref "U101") (pin "17") (pinfunction "PC2_17") (pintype "power_in"))
    )
    (net (code "63") (name "PC3") (class "Default")
      (node (ref "U101") (pin "18") (pinfunction "PC3_18") (pintype "power_in"))
    )
    (net (code "64") (name "PC4") (class "Default")
      (node (ref "U101") (pin "33") (pinfunction "PC4_33") (pintype "power_in"))
    )
    (net (code "65") (name "PC5") (class "Default")
      (node (ref "U101") (pin "34") (pinfunction "PC5_34") (pintype "power_in"))
    )
    (net (code "66") (name "PC8") (class "Default")
      (node (ref "U101") (pin "65") (pinfunction "PC8_65") (pintype "power_in"))
    )
    (net (code "67") (name "PC10") (class "Default")
      (node (ref "U101") (pin "78") (pinfunction "PC10_78") (pintype "power_in"))
    )
    (net (code "68") (name "PC11") (class "Default")
      (node (ref "U101") (pin "79") (pinfunction "PC11_79") (pintype "power_in"))
    )
    (net (code "69") (name "PC12") (class "Default")
      (node (ref "U101") (pin "80") (pinfunction "PC12_80") (pintype "power_in"))
    )
    (net (code "70") (name "PC13") (class "Default")
      (node (ref "U101") (pin "7") (pinfunction "PC13_7") (pintype "power_in"))
    )
    (net (code "71") (name "PC14") (class "Default")
      (node (ref "U101") (pin "8") (pinfunction "PC14_8") (pintype "power_in"))
    )
    (net (code "72") (name "PC15") (class "Default")
      (node (ref "U101") (pin "9") (pinfunction "PC15_9") (pintype "power_in"))
    )
    (net (code "73") (name "PD2") (class "Default")
      (node (ref "IC1") (pin "14") (pinfunction "14_14") (pintype "bidirectional"))
      (node (ref "U101") (pin "83") (pinfunction "PD2_83") (pintype "power_in"))
    )
    (net (code "74") (name "PD7") (class "Default")
      (node (ref "U101") (pin "88") (pinfunction "PD7_88") (pintype "power_in"))
    )
    (net (code "75") (name "PD8") (class "Default")
      (node (ref "U101") (pin "55") (pinfunction "PD8_55") (pintype "power_in"))
    )
    (net (code "76") (name "PD9") (class "Default")
      (node (ref "U101") (pin "56") (pinfunction "PD9_56") (pintype "power_in"))
    )
    (net (code "77") (name "PD10") (class "Default")
      (node (ref "U101") (pin "57") (pinfunction "PD10_57") (pintype "power_in"))
    )
    (net (code "78") (name "PD11") (class "Default")
      (node (ref "U101") (pin "58") (pinfunction "PD11_58") (pintype "power_in"))
    )
    (net (code "79") (name "PD12") (class "Default")
      (node (ref "U101") (pin "59") (pinfunction "PD12_59") (pintype "power_in"))
    )
    (net (code "80") (name "PD13") (class "Default")
      (node (ref "U101") (pin "60") (pinfunction "PD13_60") (pintype "power_in"))
    )
    (net (code "81") (name "PD14") (class "Default")
      (node (ref "U101") (pin "61") (pinfunction "PD14_61") (pintype "power_in"))
    )
    (net (code "82") (name "PD15") (class "Default")
      (node (ref "U101") (pin "62") (pinfunction "PD15_62") (pintype "power_in"))
    )
    (net (code "83") (name "PE2") (class "Default")
      (node (ref "U101") (pin "1") (pinfunction "PE2_1") (pintype "power_in"))
    )
    (net (code "84") (name "PE3") (class "Default")
      (node (ref "U101") (pin "2") (pinfunction "PE3_2") (pintype "power_in"))
    )
    (net (code "85") (name "PE4") (class "Default")
      (node (ref "U101") (pin "3") (pinfunction "PE4_3") (pintype "power_in"))
    )
    (net (code "86") (name "PE5") (class "Default")
      (node (ref "U101") (pin "4") (pinfunction "PE5_4") (pintype "power_in"))
    )
    (net (code "87") (name "PE6") (class "Default")
      (node (ref "U101") (pin "5") (pinfunction "PE6_5") (pintype "power_in"))
    )
    (net (code "88") (name "PE9") (class "Default")
      (node (ref "U101") (pin "40") (pinfunction "PE9_40") (pintype "power_in"))
    )
    (net (code "89") (name "PE10") (class "Default")
      (node (ref "U101") (pin "41") (pinfunction "PE10_41") (pintype "power_in"))
    )
    (net (code "90") (name "PE11") (class "Default")
      (node (ref "U101") (pin "42") (pinfunction "PE11_42") (pintype "power_in"))
    )
    (net (code "91") (name "PE15") (class "Default")
      (node (ref "U101") (pin "46") (pinfunction "PE15_46") (pintype "power_in"))
    )
    (net (code "92") (name "POWER_EN") (class "Default")
      (node (ref "R701") (pin "2") (pinfunction "2_2") (pintype "passive"))
      (node (ref "U404") (pin "5") (pinfunction "5_5") (pintype "bidirectional"))
      (node (ref "U701") (pin "4") (pinfunction "G_4") (pintype "bidirectional"))
    )
    (net (code "93") (name "SPI1_SCK") (class "Default")
      (node (ref "U101") (pin "30") (pinfunction "PA5_30") (pintype "power_in"))
    )
    (net (code "94") (name "SPI2_MISO") (class "Default")
      (node (ref "U101") (pin "53") (pinfunction "PB14_53") (pintype "power_in"))
    )
    (net (code "95") (name "SPI2_MOSI") (class "Default")
      (node (ref "U101") (pin "54") (pinfunction "PB15_54") (pintype "power_in"))
    )
    (net (code "96") (name "SPI2_SCK") (class "Default")
      (node (ref "U101") (pin "52") (pinfunction "PB13_52") (pintype "power_in"))
    )
    (net (code "97") (name "SPI4_MISO") (class "Default")
      (node (ref "U101") (pin "44") (pinfunction "PE13_44") (pintype "power_in"))
    )
    (net (code "98") (name "SPI4_MOSI") (class "Default")
      (node (ref "U101") (pin "45") (pinfunction "PE14_45") (pintype "power_in"))
    )
    (net (code "99") (name "SPI4_SCK") (class "Default")
      (node (ref "U101") (pin "43") (pinfunction "PE12_43") (pintype "power_in"))
    )
    (net (code "100") (name "TIM3_CH1") (class "Default")
      (node (ref "ESC2") (pin "PWM") (pinfunction "PWM_PWM") (pintype "bidirectional"))
      (node (ref "U101") (pin "31") (pinfunction "PA6_31") (pintype "power_in"))
    )
    (net (code "101") (name "TIM3_CH2") (class "Default")
      (node (ref "ESC3") (pin "PWM") (pinfunction "PWM_PWM") (pintype "bidirectional"))
      (node (ref "U101") (pin "32") (pinfunction "PA7_32") (pintype "power_in"))
    )
    (net (code "102") (name "TIM3_CH3") (class "Default")
      (node (ref "ESC4") (pin "PWM") (pinfunction "PWM_PWM") (pintype "bidirectional"))
      (node (ref "U101") (pin "35") (pinfunction "PB0_35") (pintype "power_in"))
    )
    (net (code "103") (name "TIM3_CH4") (class "Default")
      (node (ref "ESC1") (pin "PWM") (pinfunction "PWM_PWM") (pintype "bidirectional"))
      (node (ref "U101") (pin "66") (pinfunction "PC9_66") (pintype "power_in"))
    )
    (net (code "104") (name "UART4_RX") (class "Default")
      (node (ref "U101") (pin "24") (pinfunction "PA1_24") (pintype "power_in"))
    )
    (net (code "105") (name "UART4_TX") (class "Default")
      (node (ref "U101") (pin "23") (pinfunction "PA0_23") (pintype "power_in"))
    )
    (net (code "106") (name "UART7_RX") (class "Default")
      (node (ref "U101") (pin "38") (pinfunction "PE7_38") (pintype "power_in"))
    )
    (net (code "107") (name "UART7_TX") (class "Default")
      (node (ref "U101") (pin "39") (pinfunction "PE8_39") (pintype "power_in"))
    )
    (net (code "108") (name "UART8_RX") (class "Default")
      (node (ref "U101") (pin "97") (pinfunction "PE0_97") (pintype "power_in"))
    )
    (net (code "109") (name "UART8_TX") (class "Default")
      (node (ref "U101") (pin "98") (pinfunction "PE1_98") (pintype "power_in"))
    )
    (net (code "110") (name "USART1_CTS") (class "Default")
      (node (ref "U101") (pin "70") (pinfunction "PA11_70") (pintype "power_in"))
    )
    (net (code "111") (name "USART1_RTS") (class "Default")
      (node (ref "U101") (pin "71") (pinfunction "PA12_71") (pintype "power_in"))
    )
    (net (code "112") (name "USART1_RX") (class "Default")
      (node (ref "JP1") (pin "1") (pinfunction "1_1") (pintype "passive"))
      (node (ref "U101") (pin "69") (pinfunction "PA10_69") (pintype "power_in"))
      (node (ref "U401") (pin "1") (pinfunction "TXD_1") (pintype "bidirectional"))
    )
    (net (code "113") (name "USART1_TX") (class "Default")
      (node (ref "JP1") (pin "2") (pinfunction "2_2") (pintype "passive"))
      (node (ref "U101") (pin "68") (pinfunction "PA9_68") (pintype "power_in"))
      (node (ref "U401") (pin "5") (pinfunction "RXD_5") (pintype "bidirectional"))
    )
    (net (code "114") (name "USART2_CTS") (class "Default")
      (node (ref "U101") (pin "84") (pinfunction "PD3_84") (pintype "power_in"))
    )
    (net (code "115") (name "USART2_RTS") (class "Default")
      (node (ref "U101") (pin "85") (pinfunction "PD4_85") (pintype "power_in"))
    )
    (net (code "116") (name "USART2_RX") (class "Default")
      (node (ref "U101") (pin "87") (pinfunction "PD6_87") (pintype "power_in"))
    )
    (net (code "117") (name "USART2_TX") (class "Default")
      (node (ref "U101") (pin "86") (pinfunction "PD5_86") (pintype "power_in"))
    )
    (net (code "118") (name "USART3_RX") (class "Default")
      (node (ref "U101") (pin "48") (pinfunction "PB11_48") (pintype "power_in"))
      (node (ref "XB1") (pin "2") (pinfunction "DOUT_2") (pintype "output"))
    )
    (net (code "119") (name "USART3_TX") (class "Default")
      (node (ref "U101") (pin "47") (pinfunction "PB10_47") (pintype "power_in"))
      (node (ref "XB1") (pin "3") (pinfunction "DIN/~{CONFIG}_3") (pintype "input"))
    )
    (net (code "120") (name "USART6_RX") (class "Default")
      (node (ref "U101") (pin "64") (pinfunction "PC7_64") (pintype "power_in"))
    )
    (net (code "121") (name "USART6_TX") (class "Default")
      (node (ref "U101") (pin "63") (pinfunction "PC6_63") (pintype "power_in"))
    )
    (net (code "122") (name "USB_D_N") (class "Default")
      (node (ref "U401") (pin "16") (pinfunction "USBDM_16") (pintype "bidirectional"))
      (node (ref "U402") (pin "D-") (pinfunction "D-_D-") (pintype "bidirectional"))
    )
    (net (code "123") (name "USB_D_P") (class "Default")
      (node (ref "U401") (pin "15") (pinfunction "USBDP_15") (pintype "bidirectional"))
      (node (ref "U402") (pin "D+") (pinfunction "D+_D+") (pintype "bidirectional"))
    )
    (net (code "124") (name "VBATT") (class "Default")
      (node (ref "ESC1") (pin "VBATT") (pinfunction "VBAT_VBATT") (pintype "bidirectional"))
      (node (ref "ESC2") (pin "VBATT") (pinfunction "VBAT_VBATT") (pintype "bidirectional"))
      (node (ref "ESC3") (pin "VBATT") (pinfunction "VBAT_VBATT") (pintype "bidirectional"))
      (node (ref "ESC4") (pin "VBATT") (pinfunction "VBAT_VBATT") (pintype "bidirectional"))
      (node (ref "J701") (pin "PWR") (pinfunction "PWR_PWR") (pintype "bidirectional"))
      (node (ref "U404") (pin "1") (pinfunction "1_1") (pintype "bidirectional"))
    )
    (net (code "125") (name "VBUS") (class "Default")
      (node (ref "C402") (pin "2") (pinfunction "2_2") (pintype "passive"))
      (node (ref "C403") (pin "1") (pinfunction "1_1") (pintype "passive"))
      (node (ref "C404") (pin "1") (pinfunction "1_1") (pintype "passive"))
      (node (ref "R401") (pin "2") (pinfunction "2_2") (pintype "passive"))
      (node (ref "U401") (pin "20") (pinfunction "VCC_20") (pintype "bidirectional"))
      (node (ref "U402") (pin "VBUS") (pinfunction "VBUS_VBUS") (pintype "bidirectional"))
      (node (ref "U404") (pin "3") (pinfunction "3_3") (pintype "bidirectional"))
    )
    (net (code "126") (name "VDD_3V3") (class "Default")
      (node (ref "C201") (pin "1") (pinfunction "1_1") (pintype "passive"))
      (node (ref "C202") (pin "1") (pinfunction "1_1") (pintype "passive"))
      (node (ref "C205") (pin "1") (pinfunction "1_1") (pintype "passive"))
      (node (ref "C206") (pin "1") (pinfunction "1_1") (pintype "passive"))
      (node (ref "C207") (pin "1") (pinfunction "1_1") (pintype "passive"))
      (node (ref "C208") (pin "1") (pinfunction "1_1") (pintype "passive"))
      (node (ref "C209") (pin "1") (pinfunction "1_1") (pintype "passive"))
      (node (ref "C210") (pin "1") (pinfunction "1_1") (pintype "passive"))
      (node (ref "C211") (pin "1") (pinfunction "1_1") (pintype "passive"))
      (node (ref "C406") (pin "1") (pinfunction "1_1") (pintype "passive"))
      (node (ref "C502") (pin "2") (pinfunction "2_2") (pintype "passive"))
      (node (ref "EN") (pin "A") (pinfunction "A_A") (pintype "passive"))
      (node (ref "IC1") (pin "28") (pinfunction "28_28") (pintype "bidirectional"))
      (node (ref "IC1") (pin "3") (pinfunction "3_3") (pintype "bidirectional"))
      (node (ref "PWR") (pin "A") (pinfunction "A_A") (pintype "passive"))
      (node (ref "R201") (pin "2") (pinfunction "2_2") (pintype "passive"))
      (node (ref "R504") (pin "2") (pinfunction "2_2") (pintype "passive"))
      (node (ref "R505") (pin "1") (pinfunction "1_1") (pintype "passive"))
      (node (ref "R506") (pin "1") (pinfunction "1_1") (pintype "passive"))
      (node (ref "RX") (pin "A") (pinfunction "A_A") (pintype "passive"))
      (node (ref "TX") (pin "A") (pinfunction "A_A") (pintype "passive"))
      (node (ref "U101") (pin "100") (pinfunction "VDD_100") (pintype "power_in"))
      (node (ref "U101") (pin "11") (pinfunction "VDD_11") (pintype "power_in"))
      (node (ref "U101") (pin "19") (pinfunction "VDD_19") (pintype "power_in"))
      (node (ref "U101") (pin "21") (pinfunction "VREF+_21") (pintype "power_in"))
      (node (ref "U101") (pin "22") (pinfunction "VDDA_22") (pintype "power_in"))
      (node (ref "U101") (pin "28") (pinfunction "VDD_28") (pintype "power_in"))
      (node (ref "U101") (pin "50") (pinfunction "VDD_50") (pintype "power_in"))
      (node (ref "U101") (pin "6") (pinfunction "VBAT_6") (pintype "power_in"))
      (node (ref "U101") (pin "75") (pinfunction "VDD_75") (pintype "power_in"))
      (node (ref "U202") (pin "5") (pinfunction "VCC_5") (pintype "bidirectional"))
      (node (ref "U203") (pin "5") (pinfunction "VCC_5") (pintype "bidirectional"))
      (node (ref "U401") (pin "4") (pinfunction "VCCIO_4") (pintype "bidirectional"))
      (node (ref "U403") (pin "2") (pinfunction "3V3_2") (pintype "bidirectional"))
      (node (ref "U403") (pin "4") (pinfunction "3V3_4") (pintype "bidirectional"))
      (node (ref "XB1") (pin "1") (pinfunction "VCC_1") (pintype "power_in"))
    )
    (net (code "127") (name "XBEE_DIO0") (class "Default")
      (node (ref "U202") (pin "1") (pinfunction "A_1") (pintype "bidirectional"))
      (node (ref "XB1") (pin "20") (pinfunction "AD0/DIO0_20") (pintype "bidirectional"))
    )
    (net (code "128") (name "XBEE_DIO1") (class "Default")
      (node (ref "U203") (pin "1") (pinfunction "A_1") (pintype "bidirectional"))
      (node (ref "XB1") (pin "19") (pinfunction "AD1/DIO1_19") (pintype "bidirectional"))
    )
    (net (code "129") (name "XBEE_DIO4") (class "Default")
      (node (ref "U404") (pin "4") (pinfunction "4_4") (pintype "bidirectional"))
      (node (ref "XB1") (pin "11") (pinfunction "RF_TX/AD4/DIO4_11") (pintype "bidirectional"))
    )
    (net (code "130") (name "unconnected-(IC1-Pad7)") (class "Default")
      (node (ref "IC1") (pin "7") (pinfunction "7_7") (pintype "bidirectional"))
    )
    (net (code "131") (name "unconnected-(IC1-Pad8)") (class "Default")
      (node (ref "IC1") (pin "8") (pinfunction "8_8") (pintype "bidirectional"))
    )
    (net (code "132") (name "unconnected-(IC1-Pad11)") (class "Default")
      (node (ref "IC1") (pin "11") (pinfunction "11_11") (pintype "bidirectional"))
    )
    (net (code "133") (name "unconnected-(U401-CBUS2-Pad13)") (class "Default")
      (node (ref "U401") (pin "13") (pinfunction "CBUS2_13") (pintype "bidirectional"))
    )
    (net (code "134") (name "unconnected-(U401-CBUS3-Pad14)") (class "Default")
      (node (ref "U401") (pin "14") (pinfunction "CBUS3_14") (pintype "bidirectional"))
    )
    (net (code "135") (name "unconnected-(U401-CBUS4-Pad12)") (class "Default")
      (node (ref "U401") (pin "12") (pinfunction "CBUS4_12") (pintype "bidirectional"))
    )
    (net (code "136") (name "unconnected-(U401-CTS#-Pad11)") (class "Default")
      (node (ref "U401") (pin "11") (pinfunction "CTS#_11") (pintype "bidirectional"))
    )
    (net (code "137") (name "unconnected-(U401-DCD#-Pad10)") (class "Default")
      (node (ref "U401") (pin "10") (pinfunction "DCD#_10") (pintype "bidirectional"))
    )
    (net (code "138") (name "unconnected-(U401-DSR#-Pad9)") (class "Default")
      (node (ref "U401") (pin "9") (pinfunction "DSR#_9") (pintype "bidirectional"))
    )
    (net (code "139") (name "unconnected-(U401-OSCI-Pad27)") (class "Default")
      (node (ref "U401") (pin "27") (pinfunction "OSCI_27") (pintype "bidirectional"))
    )
    (net (code "140") (name "unconnected-(U401-OSCO-Pad28)") (class "Default")
      (node (ref "U401") (pin "28") (pinfunction "OSCO_28") (pintype "bidirectional"))
    )
    (net (code "141") (name "unconnected-(U401-RI#-Pad6)") (class "Default")
      (node (ref "U401") (pin "6") (pinfunction "RI#_6") (pintype "bidirectional"))
    )
    (net (code "142") (name "unconnected-(U402-USBID-PadID)") (class "Default")
      (node (ref "U402") (pin "ID") (pinfunction "USBID_ID") (pintype "bidirectional"))
    )
    (net (code "143") (name "unconnected-(U404-Pad6)") (class "Default")
      (node (ref "U404") (pin "6") (pinfunction "6_6") (pintype "bidirectional"))
    )
    (net (code "144") (name "unconnected-(XB1-AD2{slash}DIO2-Pad18)") (class "Default")
      (node (ref "XB1") (pin "18") (pinfunction "AD2/DIO2_18") (pintype "bidirectional"))
    )
    (net (code "145") (name "unconnected-(XB1-CD{slash}DOUT_EN{slash}DO8-Pad4)") (class "Default")
      (node (ref "XB1") (pin "4") (pinfunction "CD/DOUT_EN/DO8_4") (pintype "output"))
    )
    (net (code "146") (name "unconnected-(XB1-COORD_SEL{slash}AD3{slash}DIO3-Pad17)") (class "Default")
      (node (ref "XB1") (pin "17") (pinfunction "COORD_SEL/AD3/DIO3_17") (pintype "bidirectional"))
    )
    (net (code "147") (name "unconnected-(XB1-ON{slash}~{SLEEP}-Pad13)") (class "Default")
      (node (ref "XB1") (pin "13") (pinfunction "ON/~{SLEEP}_13") (pintype "output"))
    )
    (net (code "148") (name "unconnected-(XB1-PWM0{slash}RSSI-Pad6)") (class "Default")
      (node (ref "XB1") (pin "6") (pinfunction "PWM0/RSSI_6") (pintype "output"))
    )
    (net (code "149") (name "unconnected-(XB1-VREF-Pad14)") (class "Default")
      (node (ref "XB1") (pin "14") (pinfunction "VREF_14") (pintype "input"))
    )
    (net (code "150") (name "unconnected-(XB1-~{CTS}{slash}DIO7-Pad12)") (class "Default")
      (node (ref "XB1") (pin "12") (pinfunction "~{CTS}/DIO7_12") (pintype "bidirectional"))
    )
    (net (code "151") (name "unconnected-(XB1-~{DTR}{slash}SLEEP_RQ{slash}DI8-Pad9)") (class "Default")
      (node (ref "XB1") (pin "9") (pinfunction "~{DTR}/SLEEP_RQ/DI8_9") (pintype "bidirectional"))
    )
    (net (code "152") (name "unconnected-(XB1-~{RESET}-Pad5)") (class "Default")
      (node (ref "XB1") (pin "5") (pinfunction "~{RESET}_5") (pintype "input"))
    )
    (net (code "153") (name "unconnected-(XB1-~{RTS}{slash}AD6{slash}DIO6-Pad16)") (class "Default")
      (node (ref "XB1") (pin "16") (pinfunction "~{RTS}/AD6/DIO6_16") (pintype "bidirectional"))
    )
  )
)
